# ASIC_3.net
KiCad netlist of a schematic drawn in Altium Designer
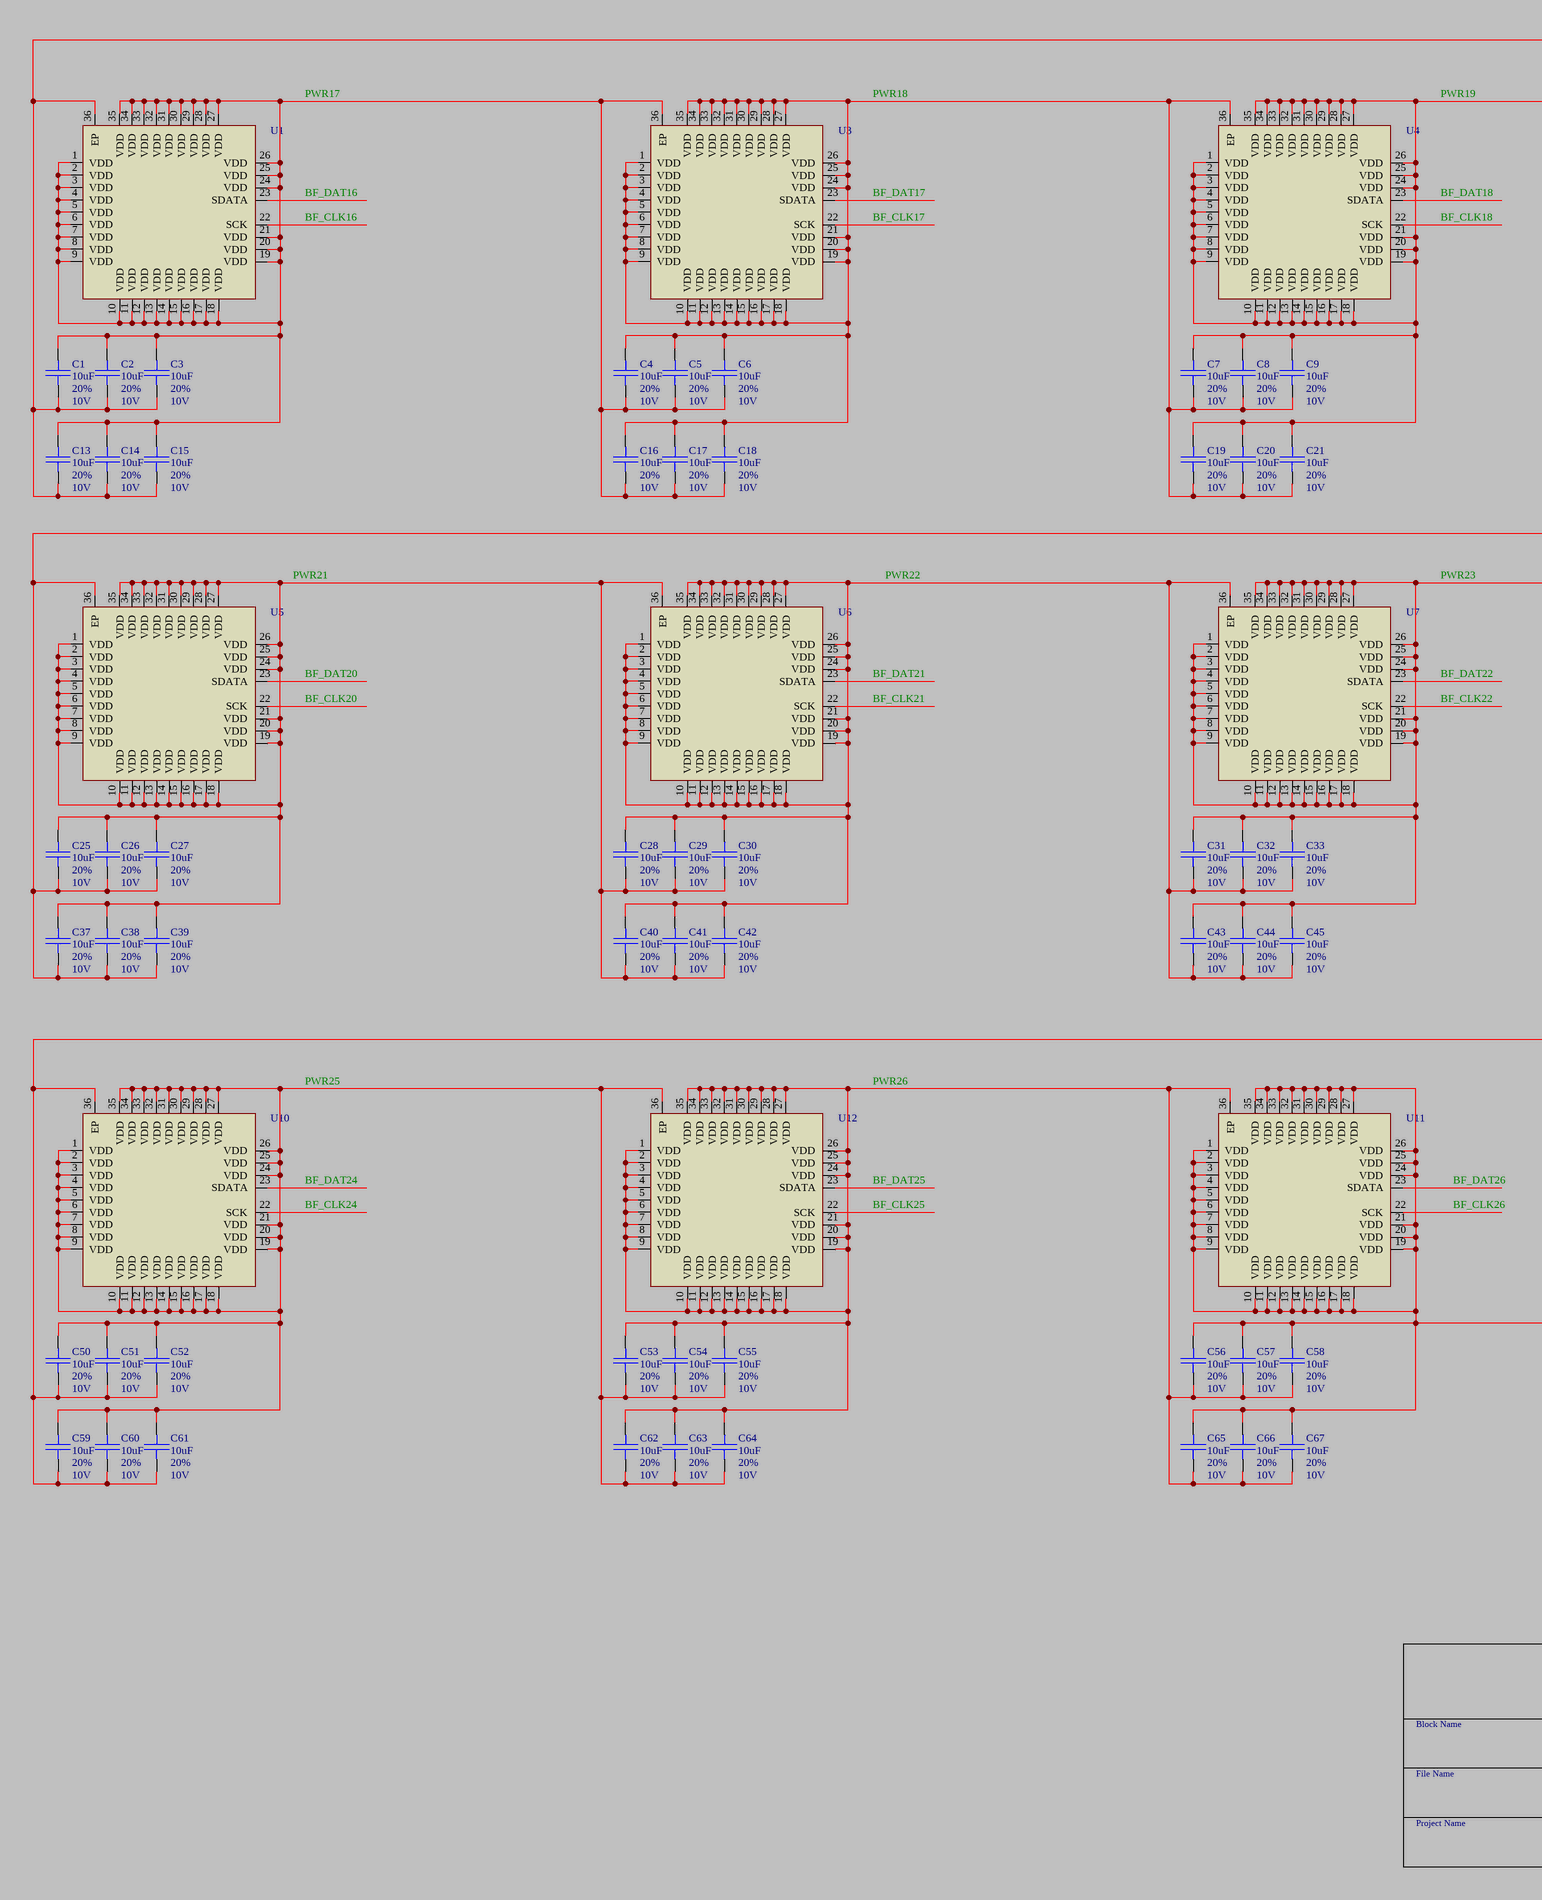
[diagram p0: ASIC_3.SchDoc, left]
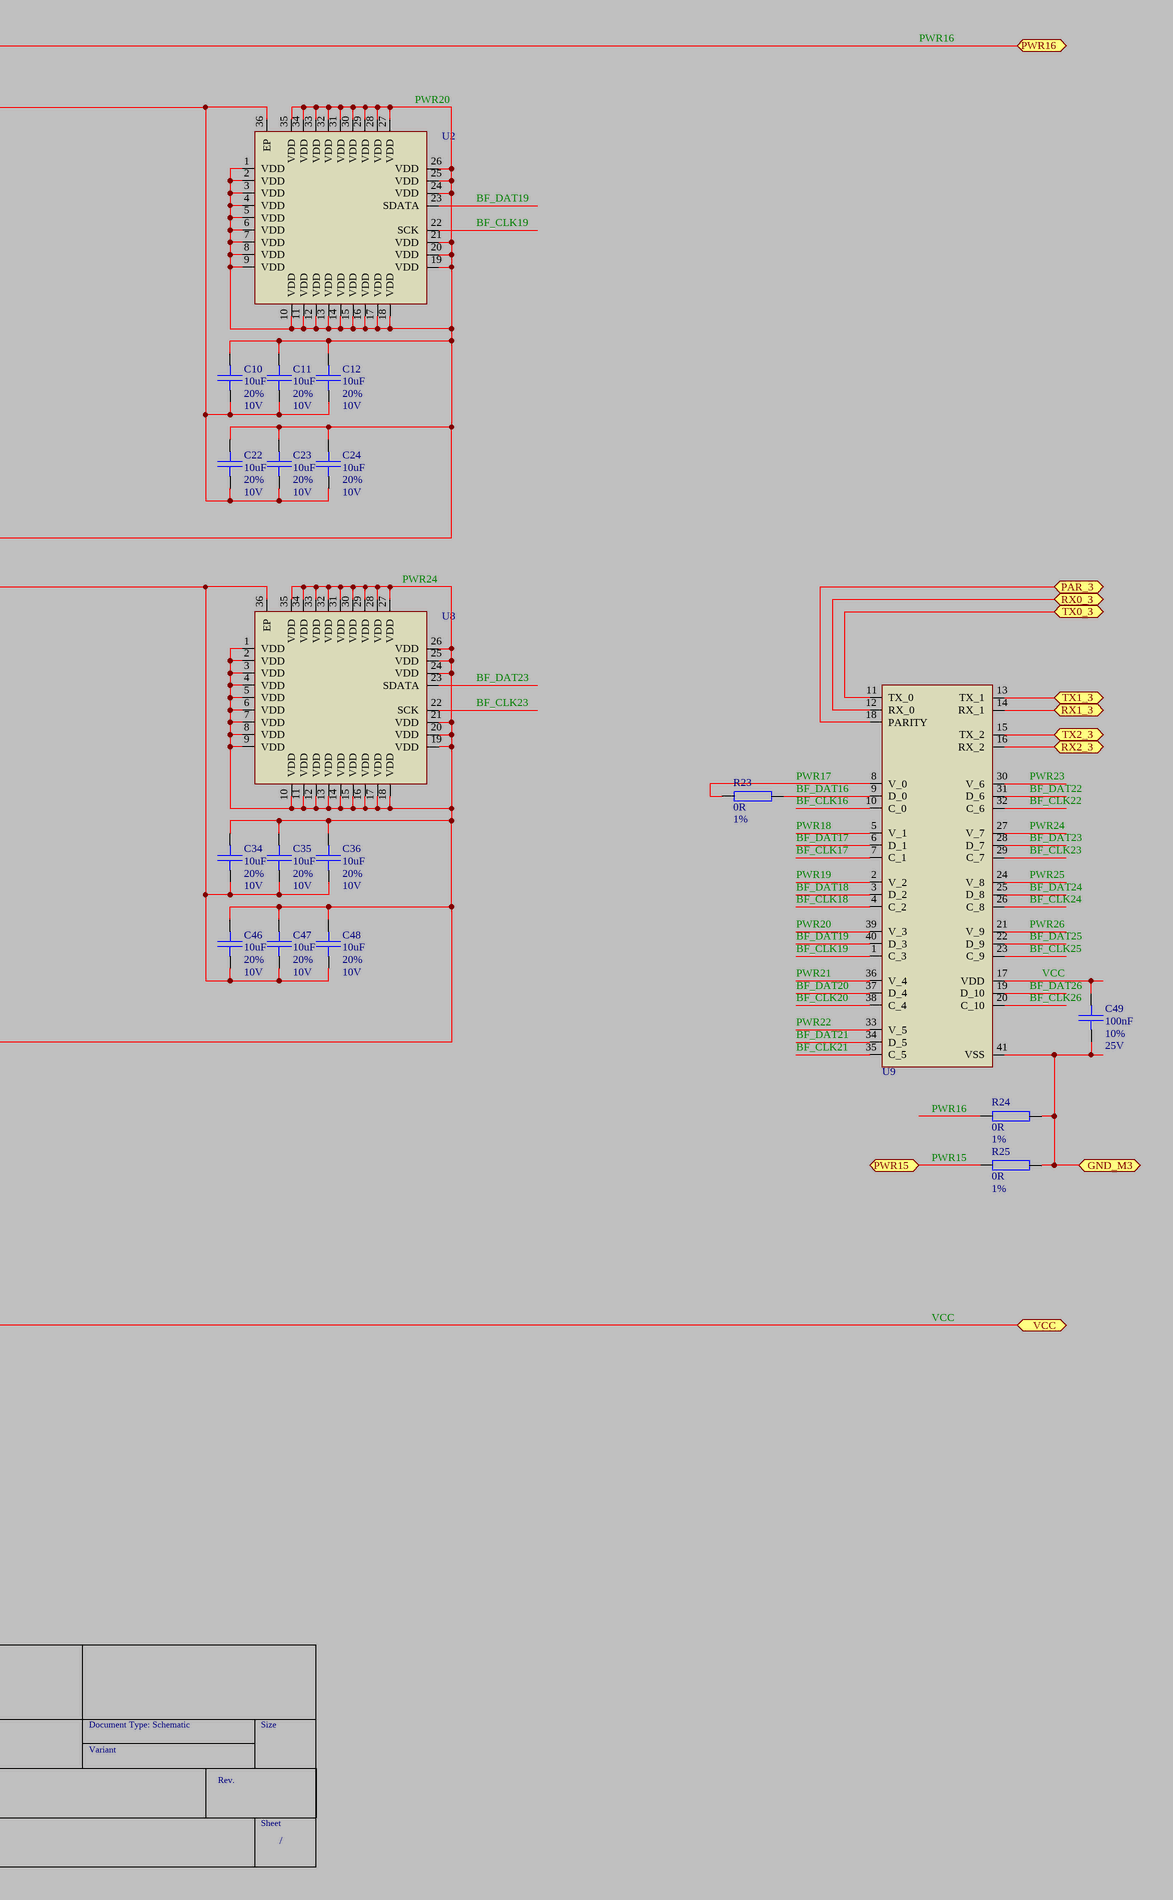
[diagram p1: ASIC_3.SchDoc, right]

(export (version "E")
  (design (tool "Eeschema 10.0.6"))
  (components
    (comp (ref "C1")
      (value "C")
      (footprint "SMD_0402_CAPC1005X70N")
      (fields
        (field (name "DB_PART_NUMBER") "CAP000047481")
        (field (name "DB_VALUE") "10uF")
        (field (name "DB_TOLERANCE") "20%")
        (field (name "DB_VOLTAGE") "10V")
        (field (name "DB_MANUFACTURER_PART") "SAMSUNG    CL05A106MP5NUNC")
        (field (name "DB_APPROVED_BY") "VSN")
      )
      (libsource (lib "Database_Libs1") (part "C"))
    )
    (comp (ref "C2")
      (value "C")
      (footprint "SMD_0402_CAPC1005X70N")
      (fields
        (field (name "DB_PART_NUMBER") "CAP000047481")
        (field (name "DB_VALUE") "10uF")
        (field (name "DB_TOLERANCE") "20%")
        (field (name "DB_VOLTAGE") "10V")
        (field (name "DB_MANUFACTURER_PART") "SAMSUNG    CL05A106MP5NUNC")
        (field (name "DB_APPROVED_BY") "VSN")
      )
      (libsource (lib "Database_Libs1") (part "C"))
    )
    (comp (ref "C3")
      (value "C")
      (footprint "SMD_0402_CAPC1005X70N")
      (fields
        (field (name "DB_PART_NUMBER") "CAP000047481")
        (field (name "DB_VALUE") "10uF")
        (field (name "DB_TOLERANCE") "20%")
        (field (name "DB_VOLTAGE") "10V")
        (field (name "DB_MANUFACTURER_PART") "SAMSUNG    CL05A106MP5NUNC")
        (field (name "DB_APPROVED_BY") "VSN")
      )
      (libsource (lib "Database_Libs1") (part "C"))
    )
    (comp (ref "C4")
      (value "C")
      (footprint "SMD_0402_CAPC1005X70N")
      (fields
        (field (name "DB_PART_NUMBER") "CAP000047481")
        (field (name "DB_VALUE") "10uF")
        (field (name "DB_TOLERANCE") "20%")
        (field (name "DB_VOLTAGE") "10V")
        (field (name "DB_MANUFACTURER_PART") "SAMSUNG    CL05A106MP5NUNC")
        (field (name "DB_APPROVED_BY") "VSN")
      )
      (libsource (lib "Database_Libs1") (part "C"))
    )
    (comp (ref "C5")
      (value "C")
      (footprint "SMD_0402_CAPC1005X70N")
      (fields
        (field (name "DB_PART_NUMBER") "CAP000047481")
        (field (name "DB_VALUE") "10uF")
        (field (name "DB_TOLERANCE") "20%")
        (field (name "DB_VOLTAGE") "10V")
        (field (name "DB_MANUFACTURER_PART") "SAMSUNG    CL05A106MP5NUNC")
        (field (name "DB_APPROVED_BY") "VSN")
      )
      (libsource (lib "Database_Libs1") (part "C"))
    )
    (comp (ref "C6")
      (value "C")
      (footprint "SMD_0402_CAPC1005X70N")
      (fields
        (field (name "DB_PART_NUMBER") "CAP000047481")
        (field (name "DB_VALUE") "10uF")
        (field (name "DB_TOLERANCE") "20%")
        (field (name "DB_VOLTAGE") "10V")
        (field (name "DB_MANUFACTURER_PART") "SAMSUNG    CL05A106MP5NUNC")
        (field (name "DB_APPROVED_BY") "VSN")
      )
      (libsource (lib "Database_Libs1") (part "C"))
    )
    (comp (ref "C7")
      (value "C")
      (footprint "SMD_0402_CAPC1005X70N")
      (fields
        (field (name "DB_PART_NUMBER") "CAP000047481")
        (field (name "DB_VALUE") "10uF")
        (field (name "DB_TOLERANCE") "20%")
        (field (name "DB_VOLTAGE") "10V")
        (field (name "DB_MANUFACTURER_PART") "SAMSUNG    CL05A106MP5NUNC")
        (field (name "DB_APPROVED_BY") "VSN")
      )
      (libsource (lib "Database_Libs1") (part "C"))
    )
    (comp (ref "C8")
      (value "C")
      (footprint "SMD_0402_CAPC1005X70N")
      (fields
        (field (name "DB_PART_NUMBER") "CAP000047481")
        (field (name "DB_VALUE") "10uF")
        (field (name "DB_TOLERANCE") "20%")
        (field (name "DB_VOLTAGE") "10V")
        (field (name "DB_MANUFACTURER_PART") "SAMSUNG    CL05A106MP5NUNC")
        (field (name "DB_APPROVED_BY") "VSN")
      )
      (libsource (lib "Database_Libs1") (part "C"))
    )
    (comp (ref "C9")
      (value "C")
      (footprint "SMD_0402_CAPC1005X70N")
      (fields
        (field (name "DB_PART_NUMBER") "CAP000047481")
        (field (name "DB_VALUE") "10uF")
        (field (name "DB_TOLERANCE") "20%")
        (field (name "DB_VOLTAGE") "10V")
        (field (name "DB_MANUFACTURER_PART") "SAMSUNG    CL05A106MP5NUNC")
        (field (name "DB_APPROVED_BY") "VSN")
      )
      (libsource (lib "Database_Libs1") (part "C"))
    )
    (comp (ref "C10")
      (value "C")
      (footprint "SMD_0402_CAPC1005X70N")
      (fields
        (field (name "DB_PART_NUMBER") "CAP000047481")
        (field (name "DB_VALUE") "10uF")
        (field (name "DB_TOLERANCE") "20%")
        (field (name "DB_VOLTAGE") "10V")
        (field (name "DB_MANUFACTURER_PART") "SAMSUNG    CL05A106MP5NUNC")
        (field (name "DB_APPROVED_BY") "VSN")
      )
      (libsource (lib "Database_Libs1") (part "C"))
    )
    (comp (ref "C11")
      (value "C")
      (footprint "SMD_0402_CAPC1005X70N")
      (fields
        (field (name "DB_PART_NUMBER") "CAP000047481")
        (field (name "DB_VALUE") "10uF")
        (field (name "DB_TOLERANCE") "20%")
        (field (name "DB_VOLTAGE") "10V")
        (field (name "DB_MANUFACTURER_PART") "SAMSUNG    CL05A106MP5NUNC")
        (field (name "DB_APPROVED_BY") "VSN")
      )
      (libsource (lib "Database_Libs1") (part "C"))
    )
    (comp (ref "C12")
      (value "C")
      (footprint "SMD_0402_CAPC1005X70N")
      (fields
        (field (name "DB_PART_NUMBER") "CAP000047481")
        (field (name "DB_VALUE") "10uF")
        (field (name "DB_TOLERANCE") "20%")
        (field (name "DB_VOLTAGE") "10V")
        (field (name "DB_MANUFACTURER_PART") "SAMSUNG    CL05A106MP5NUNC")
        (field (name "DB_APPROVED_BY") "VSN")
      )
      (libsource (lib "Database_Libs1") (part "C"))
    )
    (comp (ref "C13")
      (value "C")
      (footprint "SMD_0402_CAPC1005X70N")
      (fields
        (field (name "DB_PART_NUMBER") "CAP000047481")
        (field (name "DB_VALUE") "10uF")
        (field (name "DB_TOLERANCE") "20%")
        (field (name "DB_VOLTAGE") "10V")
        (field (name "DB_MANUFACTURER_PART") "SAMSUNG    CL05A106MP5NUNC")
        (field (name "DB_APPROVED_BY") "VSN")
      )
      (libsource (lib "Database_Libs1") (part "C"))
    )
    (comp (ref "C14")
      (value "C")
      (footprint "SMD_0402_CAPC1005X70N")
      (fields
        (field (name "DB_PART_NUMBER") "CAP000047481")
        (field (name "DB_VALUE") "10uF")
        (field (name "DB_TOLERANCE") "20%")
        (field (name "DB_VOLTAGE") "10V")
        (field (name "DB_MANUFACTURER_PART") "SAMSUNG    CL05A106MP5NUNC")
        (field (name "DB_APPROVED_BY") "VSN")
      )
      (libsource (lib "Database_Libs1") (part "C"))
    )
    (comp (ref "C15")
      (value "C")
      (footprint "SMD_0402_CAPC1005X70N")
      (fields
        (field (name "DB_PART_NUMBER") "CAP000047481")
        (field (name "DB_VALUE") "10uF")
        (field (name "DB_TOLERANCE") "20%")
        (field (name "DB_VOLTAGE") "10V")
        (field (name "DB_MANUFACTURER_PART") "SAMSUNG    CL05A106MP5NUNC")
        (field (name "DB_APPROVED_BY") "VSN")
      )
      (libsource (lib "Database_Libs1") (part "C"))
    )
    (comp (ref "C16")
      (value "C")
      (footprint "SMD_0402_CAPC1005X70N")
      (fields
        (field (name "DB_PART_NUMBER") "CAP000047481")
        (field (name "DB_VALUE") "10uF")
        (field (name "DB_TOLERANCE") "20%")
        (field (name "DB_VOLTAGE") "10V")
        (field (name "DB_MANUFACTURER_PART") "SAMSUNG    CL05A106MP5NUNC")
        (field (name "DB_APPROVED_BY") "VSN")
      )
      (libsource (lib "Database_Libs1") (part "C"))
    )
    (comp (ref "C17")
      (value "C")
      (footprint "SMD_0402_CAPC1005X70N")
      (fields
        (field (name "DB_PART_NUMBER") "CAP000047481")
        (field (name "DB_VALUE") "10uF")
        (field (name "DB_TOLERANCE") "20%")
        (field (name "DB_VOLTAGE") "10V")
        (field (name "DB_MANUFACTURER_PART") "SAMSUNG    CL05A106MP5NUNC")
        (field (name "DB_APPROVED_BY") "VSN")
      )
      (libsource (lib "Database_Libs1") (part "C"))
    )
    (comp (ref "C18")
      (value "C")
      (footprint "SMD_0402_CAPC1005X70N")
      (fields
        (field (name "DB_PART_NUMBER") "CAP000047481")
        (field (name "DB_VALUE") "10uF")
        (field (name "DB_TOLERANCE") "20%")
        (field (name "DB_VOLTAGE") "10V")
        (field (name "DB_MANUFACTURER_PART") "SAMSUNG    CL05A106MP5NUNC")
        (field (name "DB_APPROVED_BY") "VSN")
      )
      (libsource (lib "Database_Libs1") (part "C"))
    )
    (comp (ref "C19")
      (value "C")
      (footprint "SMD_0402_CAPC1005X70N")
      (fields
        (field (name "DB_PART_NUMBER") "CAP000047481")
        (field (name "DB_VALUE") "10uF")
        (field (name "DB_TOLERANCE") "20%")
        (field (name "DB_VOLTAGE") "10V")
        (field (name "DB_MANUFACTURER_PART") "SAMSUNG    CL05A106MP5NUNC")
        (field (name "DB_APPROVED_BY") "VSN")
      )
      (libsource (lib "Database_Libs1") (part "C"))
    )
    (comp (ref "C20")
      (value "C")
      (footprint "SMD_0402_CAPC1005X70N")
      (fields
        (field (name "DB_PART_NUMBER") "CAP000047481")
        (field (name "DB_VALUE") "10uF")
        (field (name "DB_TOLERANCE") "20%")
        (field (name "DB_VOLTAGE") "10V")
        (field (name "DB_MANUFACTURER_PART") "SAMSUNG    CL05A106MP5NUNC")
        (field (name "DB_APPROVED_BY") "VSN")
      )
      (libsource (lib "Database_Libs1") (part "C"))
    )
    (comp (ref "C21")
      (value "C")
      (footprint "SMD_0402_CAPC1005X70N")
      (fields
        (field (name "DB_PART_NUMBER") "CAP000047481")
        (field (name "DB_VALUE") "10uF")
        (field (name "DB_TOLERANCE") "20%")
        (field (name "DB_VOLTAGE") "10V")
        (field (name "DB_MANUFACTURER_PART") "SAMSUNG    CL05A106MP5NUNC")
        (field (name "DB_APPROVED_BY") "VSN")
      )
      (libsource (lib "Database_Libs1") (part "C"))
    )
    (comp (ref "C22")
      (value "C")
      (footprint "SMD_0402_CAPC1005X70N")
      (fields
        (field (name "DB_PART_NUMBER") "CAP000047481")
        (field (name "DB_VALUE") "10uF")
        (field (name "DB_TOLERANCE") "20%")
        (field (name "DB_VOLTAGE") "10V")
        (field (name "DB_MANUFACTURER_PART") "SAMSUNG    CL05A106MP5NUNC")
        (field (name "DB_APPROVED_BY") "VSN")
      )
      (libsource (lib "Database_Libs1") (part "C"))
    )
    (comp (ref "C23")
      (value "C")
      (footprint "SMD_0402_CAPC1005X70N")
      (fields
        (field (name "DB_PART_NUMBER") "CAP000047481")
        (field (name "DB_VALUE") "10uF")
        (field (name "DB_TOLERANCE") "20%")
        (field (name "DB_VOLTAGE") "10V")
        (field (name "DB_MANUFACTURER_PART") "SAMSUNG    CL05A106MP5NUNC")
        (field (name "DB_APPROVED_BY") "VSN")
      )
      (libsource (lib "Database_Libs1") (part "C"))
    )
    (comp (ref "C24")
      (value "C")
      (footprint "SMD_0402_CAPC1005X70N")
      (fields
        (field (name "DB_PART_NUMBER") "CAP000047481")
        (field (name "DB_VALUE") "10uF")
        (field (name "DB_TOLERANCE") "20%")
        (field (name "DB_VOLTAGE") "10V")
        (field (name "DB_MANUFACTURER_PART") "SAMSUNG    CL05A106MP5NUNC")
        (field (name "DB_APPROVED_BY") "VSN")
      )
      (libsource (lib "Database_Libs1") (part "C"))
    )
    (comp (ref "C25")
      (value "C")
      (footprint "SMD_0402_CAPC1005X70N")
      (fields
        (field (name "DB_PART_NUMBER") "CAP000047481")
        (field (name "DB_VALUE") "10uF")
        (field (name "DB_TOLERANCE") "20%")
        (field (name "DB_VOLTAGE") "10V")
        (field (name "DB_MANUFACTURER_PART") "SAMSUNG    CL05A106MP5NUNC")
        (field (name "DB_APPROVED_BY") "VSN")
      )
      (libsource (lib "Database_Libs1") (part "C"))
    )
    (comp (ref "C26")
      (value "C")
      (footprint "SMD_0402_CAPC1005X70N")
      (fields
        (field (name "DB_PART_NUMBER") "CAP000047481")
        (field (name "DB_VALUE") "10uF")
        (field (name "DB_TOLERANCE") "20%")
        (field (name "DB_VOLTAGE") "10V")
        (field (name "DB_MANUFACTURER_PART") "SAMSUNG    CL05A106MP5NUNC")
        (field (name "DB_APPROVED_BY") "VSN")
      )
      (libsource (lib "Database_Libs1") (part "C"))
    )
    (comp (ref "C27")
      (value "C")
      (footprint "SMD_0402_CAPC1005X70N")
      (fields
        (field (name "DB_PART_NUMBER") "CAP000047481")
        (field (name "DB_VALUE") "10uF")
        (field (name "DB_TOLERANCE") "20%")
        (field (name "DB_VOLTAGE") "10V")
        (field (name "DB_MANUFACTURER_PART") "SAMSUNG    CL05A106MP5NUNC")
        (field (name "DB_APPROVED_BY") "VSN")
      )
      (libsource (lib "Database_Libs1") (part "C"))
    )
    (comp (ref "C28")
      (value "C")
      (footprint "SMD_0402_CAPC1005X70N")
      (fields
        (field (name "DB_PART_NUMBER") "CAP000047481")
        (field (name "DB_VALUE") "10uF")
        (field (name "DB_TOLERANCE") "20%")
        (field (name "DB_VOLTAGE") "10V")
        (field (name "DB_MANUFACTURER_PART") "SAMSUNG    CL05A106MP5NUNC")
        (field (name "DB_APPROVED_BY") "VSN")
      )
      (libsource (lib "Database_Libs1") (part "C"))
    )
    (comp (ref "C29")
      (value "C")
      (footprint "SMD_0402_CAPC1005X70N")
      (fields
        (field (name "DB_PART_NUMBER") "CAP000047481")
        (field (name "DB_VALUE") "10uF")
        (field (name "DB_TOLERANCE") "20%")
        (field (name "DB_VOLTAGE") "10V")
        (field (name "DB_MANUFACTURER_PART") "SAMSUNG    CL05A106MP5NUNC")
        (field (name "DB_APPROVED_BY") "VSN")
      )
      (libsource (lib "Database_Libs1") (part "C"))
    )
    (comp (ref "C30")
      (value "C")
      (footprint "SMD_0402_CAPC1005X70N")
      (fields
        (field (name "DB_PART_NUMBER") "CAP000047481")
        (field (name "DB_VALUE") "10uF")
        (field (name "DB_TOLERANCE") "20%")
        (field (name "DB_VOLTAGE") "10V")
        (field (name "DB_MANUFACTURER_PART") "SAMSUNG    CL05A106MP5NUNC")
        (field (name "DB_APPROVED_BY") "VSN")
      )
      (libsource (lib "Database_Libs1") (part "C"))
    )
    (comp (ref "C31")
      (value "C")
      (footprint "SMD_0402_CAPC1005X70N")
      (fields
        (field (name "DB_PART_NUMBER") "CAP000047481")
        (field (name "DB_VALUE") "10uF")
        (field (name "DB_TOLERANCE") "20%")
        (field (name "DB_VOLTAGE") "10V")
        (field (name "DB_MANUFACTURER_PART") "SAMSUNG    CL05A106MP5NUNC")
        (field (name "DB_APPROVED_BY") "VSN")
      )
      (libsource (lib "Database_Libs1") (part "C"))
    )
    (comp (ref "C32")
      (value "C")
      (footprint "SMD_0402_CAPC1005X70N")
      (fields
        (field (name "DB_PART_NUMBER") "CAP000047481")
        (field (name "DB_VALUE") "10uF")
        (field (name "DB_TOLERANCE") "20%")
        (field (name "DB_VOLTAGE") "10V")
        (field (name "DB_MANUFACTURER_PART") "SAMSUNG    CL05A106MP5NUNC")
        (field (name "DB_APPROVED_BY") "VSN")
      )
      (libsource (lib "Database_Libs1") (part "C"))
    )
    (comp (ref "C33")
      (value "C")
      (footprint "SMD_0402_CAPC1005X70N")
      (fields
        (field (name "DB_PART_NUMBER") "CAP000047481")
        (field (name "DB_VALUE") "10uF")
        (field (name "DB_TOLERANCE") "20%")
        (field (name "DB_VOLTAGE") "10V")
        (field (name "DB_MANUFACTURER_PART") "SAMSUNG    CL05A106MP5NUNC")
        (field (name "DB_APPROVED_BY") "VSN")
      )
      (libsource (lib "Database_Libs1") (part "C"))
    )
    (comp (ref "C34")
      (value "C")
      (footprint "SMD_0402_CAPC1005X70N")
      (fields
        (field (name "DB_PART_NUMBER") "CAP000047481")
        (field (name "DB_VALUE") "10uF")
        (field (name "DB_TOLERANCE") "20%")
        (field (name "DB_VOLTAGE") "10V")
        (field (name "DB_MANUFACTURER_PART") "SAMSUNG    CL05A106MP5NUNC")
        (field (name "DB_APPROVED_BY") "VSN")
      )
      (libsource (lib "Database_Libs1") (part "C"))
    )
    (comp (ref "C35")
      (value "C")
      (footprint "SMD_0402_CAPC1005X70N")
      (fields
        (field (name "DB_PART_NUMBER") "CAP000047481")
        (field (name "DB_VALUE") "10uF")
        (field (name "DB_TOLERANCE") "20%")
        (field (name "DB_VOLTAGE") "10V")
        (field (name "DB_MANUFACTURER_PART") "SAMSUNG    CL05A106MP5NUNC")
        (field (name "DB_APPROVED_BY") "VSN")
      )
      (libsource (lib "Database_Libs1") (part "C"))
    )
    (comp (ref "C36")
      (value "C")
      (footprint "SMD_0402_CAPC1005X70N")
      (fields
        (field (name "DB_PART_NUMBER") "CAP000047481")
        (field (name "DB_VALUE") "10uF")
        (field (name "DB_TOLERANCE") "20%")
        (field (name "DB_VOLTAGE") "10V")
        (field (name "DB_MANUFACTURER_PART") "SAMSUNG    CL05A106MP5NUNC")
        (field (name "DB_APPROVED_BY") "VSN")
      )
      (libsource (lib "Database_Libs1") (part "C"))
    )
    (comp (ref "C37")
      (value "C")
      (footprint "SMD_0402_CAPC1005X70N")
      (fields
        (field (name "DB_PART_NUMBER") "CAP000047481")
        (field (name "DB_VALUE") "10uF")
        (field (name "DB_TOLERANCE") "20%")
        (field (name "DB_VOLTAGE") "10V")
        (field (name "DB_MANUFACTURER_PART") "SAMSUNG    CL05A106MP5NUNC")
        (field (name "DB_APPROVED_BY") "VSN")
      )
      (libsource (lib "Database_Libs1") (part "C"))
    )
    (comp (ref "C38")
      (value "C")
      (footprint "SMD_0402_CAPC1005X70N")
      (fields
        (field (name "DB_PART_NUMBER") "CAP000047481")
        (field (name "DB_VALUE") "10uF")
        (field (name "DB_TOLERANCE") "20%")
        (field (name "DB_VOLTAGE") "10V")
        (field (name "DB_MANUFACTURER_PART") "SAMSUNG    CL05A106MP5NUNC")
        (field (name "DB_APPROVED_BY") "VSN")
      )
      (libsource (lib "Database_Libs1") (part "C"))
    )
    (comp (ref "C39")
      (value "C")
      (footprint "SMD_0402_CAPC1005X70N")
      (fields
        (field (name "DB_PART_NUMBER") "CAP000047481")
        (field (name "DB_VALUE") "10uF")
        (field (name "DB_TOLERANCE") "20%")
        (field (name "DB_VOLTAGE") "10V")
        (field (name "DB_MANUFACTURER_PART") "SAMSUNG    CL05A106MP5NUNC")
        (field (name "DB_APPROVED_BY") "VSN")
      )
      (libsource (lib "Database_Libs1") (part "C"))
    )
    (comp (ref "C40")
      (value "C")
      (footprint "SMD_0402_CAPC1005X70N")
      (fields
        (field (name "DB_PART_NUMBER") "CAP000047481")
        (field (name "DB_VALUE") "10uF")
        (field (name "DB_TOLERANCE") "20%")
        (field (name "DB_VOLTAGE") "10V")
        (field (name "DB_MANUFACTURER_PART") "SAMSUNG    CL05A106MP5NUNC")
        (field (name "DB_APPROVED_BY") "VSN")
      )
      (libsource (lib "Database_Libs1") (part "C"))
    )
    (comp (ref "C41")
      (value "C")
      (footprint "SMD_0402_CAPC1005X70N")
      (fields
        (field (name "DB_PART_NUMBER") "CAP000047481")
        (field (name "DB_VALUE") "10uF")
        (field (name "DB_TOLERANCE") "20%")
        (field (name "DB_VOLTAGE") "10V")
        (field (name "DB_MANUFACTURER_PART") "SAMSUNG    CL05A106MP5NUNC")
        (field (name "DB_APPROVED_BY") "VSN")
      )
      (libsource (lib "Database_Libs1") (part "C"))
    )
    (comp (ref "C42")
      (value "C")
      (footprint "SMD_0402_CAPC1005X70N")
      (fields
        (field (name "DB_PART_NUMBER") "CAP000047481")
        (field (name "DB_VALUE") "10uF")
        (field (name "DB_TOLERANCE") "20%")
        (field (name "DB_VOLTAGE") "10V")
        (field (name "DB_MANUFACTURER_PART") "SAMSUNG    CL05A106MP5NUNC")
        (field (name "DB_APPROVED_BY") "VSN")
      )
      (libsource (lib "Database_Libs1") (part "C"))
    )
    (comp (ref "C43")
      (value "C")
      (footprint "SMD_0402_CAPC1005X70N")
      (fields
        (field (name "DB_PART_NUMBER") "CAP000047481")
        (field (name "DB_VALUE") "10uF")
        (field (name "DB_TOLERANCE") "20%")
        (field (name "DB_VOLTAGE") "10V")
        (field (name "DB_MANUFACTURER_PART") "SAMSUNG    CL05A106MP5NUNC")
        (field (name "DB_APPROVED_BY") "VSN")
      )
      (libsource (lib "Database_Libs1") (part "C"))
    )
    (comp (ref "C44")
      (value "C")
      (footprint "SMD_0402_CAPC1005X70N")
      (fields
        (field (name "DB_PART_NUMBER") "CAP000047481")
        (field (name "DB_VALUE") "10uF")
        (field (name "DB_TOLERANCE") "20%")
        (field (name "DB_VOLTAGE") "10V")
        (field (name "DB_MANUFACTURER_PART") "SAMSUNG    CL05A106MP5NUNC")
        (field (name "DB_APPROVED_BY") "VSN")
      )
      (libsource (lib "Database_Libs1") (part "C"))
    )
    (comp (ref "C45")
      (value "C")
      (footprint "SMD_0402_CAPC1005X70N")
      (fields
        (field (name "DB_PART_NUMBER") "CAP000047481")
        (field (name "DB_VALUE") "10uF")
        (field (name "DB_TOLERANCE") "20%")
        (field (name "DB_VOLTAGE") "10V")
        (field (name "DB_MANUFACTURER_PART") "SAMSUNG    CL05A106MP5NUNC")
        (field (name "DB_APPROVED_BY") "VSN")
      )
      (libsource (lib "Database_Libs1") (part "C"))
    )
    (comp (ref "C46")
      (value "C")
      (footprint "SMD_0402_CAPC1005X70N")
      (fields
        (field (name "DB_PART_NUMBER") "CAP000047481")
        (field (name "DB_VALUE") "10uF")
        (field (name "DB_TOLERANCE") "20%")
        (field (name "DB_VOLTAGE") "10V")
        (field (name "DB_MANUFACTURER_PART") "SAMSUNG    CL05A106MP5NUNC")
        (field (name "DB_APPROVED_BY") "VSN")
      )
      (libsource (lib "Database_Libs1") (part "C"))
    )
    (comp (ref "C47")
      (value "C")
      (footprint "SMD_0402_CAPC1005X70N")
      (fields
        (field (name "DB_PART_NUMBER") "CAP000047481")
        (field (name "DB_VALUE") "10uF")
        (field (name "DB_TOLERANCE") "20%")
        (field (name "DB_VOLTAGE") "10V")
        (field (name "DB_MANUFACTURER_PART") "SAMSUNG    CL05A106MP5NUNC")
        (field (name "DB_APPROVED_BY") "VSN")
      )
      (libsource (lib "Database_Libs1") (part "C"))
    )
    (comp (ref "C48")
      (value "C")
      (footprint "SMD_0402_CAPC1005X70N")
      (fields
        (field (name "DB_PART_NUMBER") "CAP000047481")
        (field (name "DB_VALUE") "10uF")
        (field (name "DB_TOLERANCE") "20%")
        (field (name "DB_VOLTAGE") "10V")
        (field (name "DB_MANUFACTURER_PART") "SAMSUNG    CL05A106MP5NUNC")
        (field (name "DB_APPROVED_BY") "VSN")
      )
      (libsource (lib "Database_Libs1") (part "C"))
    )
    (comp (ref "C49")
      (value "C")
      (footprint "SMD_0402_CAPC1005X55N")
      (fields
        (field (name "DB_PART_NUMBER") "CAP000047469")
        (field (name "DB_VALUE") "100nF")
        (field (name "DB_TOLERANCE") "10%")
        (field (name "DB_VOLTAGE") "25V")
        (field (name "DB_MANUFACTURER_PART") "SAMSUNG    CL05A104KA5NNNC")
        (field (name "DB_APPROVED_BY") "VSN")
      )
      (libsource (lib "Database_Libs1") (part "C"))
    )
    (comp (ref "C50")
      (value "C")
      (footprint "SMD_0402_CAPC1005X70N")
      (fields
        (field (name "DB_PART_NUMBER") "CAP000047481")
        (field (name "DB_VALUE") "10uF")
        (field (name "DB_TOLERANCE") "20%")
        (field (name "DB_VOLTAGE") "10V")
        (field (name "DB_MANUFACTURER_PART") "SAMSUNG    CL05A106MP5NUNC")
        (field (name "DB_APPROVED_BY") "VSN")
      )
      (libsource (lib "Database_Libs1") (part "C"))
    )
    (comp (ref "C51")
      (value "C")
      (footprint "SMD_0402_CAPC1005X70N")
      (fields
        (field (name "DB_PART_NUMBER") "CAP000047481")
        (field (name "DB_VALUE") "10uF")
        (field (name "DB_TOLERANCE") "20%")
        (field (name "DB_VOLTAGE") "10V")
        (field (name "DB_MANUFACTURER_PART") "SAMSUNG    CL05A106MP5NUNC")
        (field (name "DB_APPROVED_BY") "VSN")
      )
      (libsource (lib "Database_Libs1") (part "C"))
    )
    (comp (ref "C52")
      (value "C")
      (footprint "SMD_0402_CAPC1005X70N")
      (fields
        (field (name "DB_PART_NUMBER") "CAP000047481")
        (field (name "DB_VALUE") "10uF")
        (field (name "DB_TOLERANCE") "20%")
        (field (name "DB_VOLTAGE") "10V")
        (field (name "DB_MANUFACTURER_PART") "SAMSUNG    CL05A106MP5NUNC")
        (field (name "DB_APPROVED_BY") "VSN")
      )
      (libsource (lib "Database_Libs1") (part "C"))
    )
    (comp (ref "C53")
      (value "C")
      (footprint "SMD_0402_CAPC1005X70N")
      (fields
        (field (name "DB_PART_NUMBER") "CAP000047481")
        (field (name "DB_VALUE") "10uF")
        (field (name "DB_TOLERANCE") "20%")
        (field (name "DB_VOLTAGE") "10V")
        (field (name "DB_MANUFACTURER_PART") "SAMSUNG    CL05A106MP5NUNC")
        (field (name "DB_APPROVED_BY") "VSN")
      )
      (libsource (lib "Database_Libs1") (part "C"))
    )
    (comp (ref "C54")
      (value "C")
      (footprint "SMD_0402_CAPC1005X70N")
      (fields
        (field (name "DB_PART_NUMBER") "CAP000047481")
        (field (name "DB_VALUE") "10uF")
        (field (name "DB_TOLERANCE") "20%")
        (field (name "DB_VOLTAGE") "10V")
        (field (name "DB_MANUFACTURER_PART") "SAMSUNG    CL05A106MP5NUNC")
        (field (name "DB_APPROVED_BY") "VSN")
      )
      (libsource (lib "Database_Libs1") (part "C"))
    )
    (comp (ref "C55")
      (value "C")
      (footprint "SMD_0402_CAPC1005X70N")
      (fields
        (field (name "DB_PART_NUMBER") "CAP000047481")
        (field (name "DB_VALUE") "10uF")
        (field (name "DB_TOLERANCE") "20%")
        (field (name "DB_VOLTAGE") "10V")
        (field (name "DB_MANUFACTURER_PART") "SAMSUNG    CL05A106MP5NUNC")
        (field (name "DB_APPROVED_BY") "VSN")
      )
      (libsource (lib "Database_Libs1") (part "C"))
    )
    (comp (ref "C56")
      (value "C")
      (footprint "SMD_0402_CAPC1005X70N")
      (fields
        (field (name "DB_PART_NUMBER") "CAP000047481")
        (field (name "DB_VALUE") "10uF")
        (field (name "DB_TOLERANCE") "20%")
        (field (name "DB_VOLTAGE") "10V")
        (field (name "DB_MANUFACTURER_PART") "SAMSUNG    CL05A106MP5NUNC")
        (field (name "DB_APPROVED_BY") "VSN")
      )
      (libsource (lib "Database_Libs1") (part "C"))
    )
    (comp (ref "C57")
      (value "C")
      (footprint "SMD_0402_CAPC1005X70N")
      (fields
        (field (name "DB_PART_NUMBER") "CAP000047481")
        (field (name "DB_VALUE") "10uF")
        (field (name "DB_TOLERANCE") "20%")
        (field (name "DB_VOLTAGE") "10V")
        (field (name "DB_MANUFACTURER_PART") "SAMSUNG    CL05A106MP5NUNC")
        (field (name "DB_APPROVED_BY") "VSN")
      )
      (libsource (lib "Database_Libs1") (part "C"))
    )
    (comp (ref "C58")
      (value "C")
      (footprint "SMD_0402_CAPC1005X70N")
      (fields
        (field (name "DB_PART_NUMBER") "CAP000047481")
        (field (name "DB_VALUE") "10uF")
        (field (name "DB_TOLERANCE") "20%")
        (field (name "DB_VOLTAGE") "10V")
        (field (name "DB_MANUFACTURER_PART") "SAMSUNG    CL05A106MP5NUNC")
        (field (name "DB_APPROVED_BY") "VSN")
      )
      (libsource (lib "Database_Libs1") (part "C"))
    )
    (comp (ref "C59")
      (value "C")
      (footprint "SMD_0402_CAPC1005X70N")
      (fields
        (field (name "DB_PART_NUMBER") "CAP000047481")
        (field (name "DB_VALUE") "10uF")
        (field (name "DB_TOLERANCE") "20%")
        (field (name "DB_VOLTAGE") "10V")
        (field (name "DB_MANUFACTURER_PART") "SAMSUNG    CL05A106MP5NUNC")
        (field (name "DB_APPROVED_BY") "VSN")
      )
      (libsource (lib "Database_Libs1") (part "C"))
    )
    (comp (ref "C60")
      (value "C")
      (footprint "SMD_0402_CAPC1005X70N")
      (fields
        (field (name "DB_PART_NUMBER") "CAP000047481")
        (field (name "DB_VALUE") "10uF")
        (field (name "DB_TOLERANCE") "20%")
        (field (name "DB_VOLTAGE") "10V")
        (field (name "DB_MANUFACTURER_PART") "SAMSUNG    CL05A106MP5NUNC")
        (field (name "DB_APPROVED_BY") "VSN")
      )
      (libsource (lib "Database_Libs1") (part "C"))
    )
    (comp (ref "C61")
      (value "C")
      (footprint "SMD_0402_CAPC1005X70N")
      (fields
        (field (name "DB_PART_NUMBER") "CAP000047481")
        (field (name "DB_VALUE") "10uF")
        (field (name "DB_TOLERANCE") "20%")
        (field (name "DB_VOLTAGE") "10V")
        (field (name "DB_MANUFACTURER_PART") "SAMSUNG    CL05A106MP5NUNC")
        (field (name "DB_APPROVED_BY") "VSN")
      )
      (libsource (lib "Database_Libs1") (part "C"))
    )
    (comp (ref "C62")
      (value "C")
      (footprint "SMD_0402_CAPC1005X70N")
      (fields
        (field (name "DB_PART_NUMBER") "CAP000047481")
        (field (name "DB_VALUE") "10uF")
        (field (name "DB_TOLERANCE") "20%")
        (field (name "DB_VOLTAGE") "10V")
        (field (name "DB_MANUFACTURER_PART") "SAMSUNG    CL05A106MP5NUNC")
        (field (name "DB_APPROVED_BY") "VSN")
      )
      (libsource (lib "Database_Libs1") (part "C"))
    )
    (comp (ref "C63")
      (value "C")
      (footprint "SMD_0402_CAPC1005X70N")
      (fields
        (field (name "DB_PART_NUMBER") "CAP000047481")
        (field (name "DB_VALUE") "10uF")
        (field (name "DB_TOLERANCE") "20%")
        (field (name "DB_VOLTAGE") "10V")
        (field (name "DB_MANUFACTURER_PART") "SAMSUNG    CL05A106MP5NUNC")
        (field (name "DB_APPROVED_BY") "VSN")
      )
      (libsource (lib "Database_Libs1") (part "C"))
    )
    (comp (ref "C64")
      (value "C")
      (footprint "SMD_0402_CAPC1005X70N")
      (fields
        (field (name "DB_PART_NUMBER") "CAP000047481")
        (field (name "DB_VALUE") "10uF")
        (field (name "DB_TOLERANCE") "20%")
        (field (name "DB_VOLTAGE") "10V")
        (field (name "DB_MANUFACTURER_PART") "SAMSUNG    CL05A106MP5NUNC")
        (field (name "DB_APPROVED_BY") "VSN")
      )
      (libsource (lib "Database_Libs1") (part "C"))
    )
    (comp (ref "C65")
      (value "C")
      (footprint "SMD_0402_CAPC1005X70N")
      (fields
        (field (name "DB_PART_NUMBER") "CAP000047481")
        (field (name "DB_VALUE") "10uF")
        (field (name "DB_TOLERANCE") "20%")
        (field (name "DB_VOLTAGE") "10V")
        (field (name "DB_MANUFACTURER_PART") "SAMSUNG    CL05A106MP5NUNC")
        (field (name "DB_APPROVED_BY") "VSN")
      )
      (libsource (lib "Database_Libs1") (part "C"))
    )
    (comp (ref "C66")
      (value "C")
      (footprint "SMD_0402_CAPC1005X70N")
      (fields
        (field (name "DB_PART_NUMBER") "CAP000047481")
        (field (name "DB_VALUE") "10uF")
        (field (name "DB_TOLERANCE") "20%")
        (field (name "DB_VOLTAGE") "10V")
        (field (name "DB_MANUFACTURER_PART") "SAMSUNG    CL05A106MP5NUNC")
        (field (name "DB_APPROVED_BY") "VSN")
      )
      (libsource (lib "Database_Libs1") (part "C"))
    )
    (comp (ref "C67")
      (value "C")
      (footprint "SMD_0402_CAPC1005X70N")
      (fields
        (field (name "DB_PART_NUMBER") "CAP000047481")
        (field (name "DB_VALUE") "10uF")
        (field (name "DB_TOLERANCE") "20%")
        (field (name "DB_VOLTAGE") "10V")
        (field (name "DB_MANUFACTURER_PART") "SAMSUNG    CL05A106MP5NUNC")
        (field (name "DB_APPROVED_BY") "VSN")
      )
      (libsource (lib "Database_Libs1") (part "C"))
    )
    (comp (ref "R23")
      (value "R")
      (footprint "SMD_0603_RESC1608X55N")
      (fields
        (field (name "DB_PART_NUMBER") "RES000008926")
        (field (name "DB_VALUE") "0R")
        (field (name "DB_TOLERANCE") "1%")
        (field (name "DB_MANUFACTURER_PART") "YAGEO    AC0603FR-070RL")
        (field (name "DB_APPROVED_BY") "VSN")
      )
      (libsource (lib "Database_Libs1") (part "R"))
    )
    (comp (ref "R24")
      (value "R")
      (footprint "SMD_0603_RESC1608X55N")
      (fields
        (field (name "DB_PART_NUMBER") "RES000008926")
        (field (name "DB_VALUE") "0R")
        (field (name "DB_TOLERANCE") "1%")
        (field (name "DB_MANUFACTURER_PART") "YAGEO    AC0603FR-070RL")
        (field (name "DB_APPROVED_BY") "VSN")
      )
      (libsource (lib "Database_Libs1") (part "R"))
    )
    (comp (ref "R25")
      (value "R")
      (footprint "SMD_0603_RESC1608X55N")
      (fields
        (field (name "DB_PART_NUMBER") "RES000008926")
        (field (name "DB_VALUE") "0R")
        (field (name "DB_TOLERANCE") "1%")
        (field (name "DB_MANUFACTURER_PART") "YAGEO    AC0603FR-070RL")
        (field (name "DB_APPROVED_BY") "VSN")
      )
      (libsource (lib "Database_Libs1") (part "R"))
    )
    (comp (ref "U1")
      (value "IC_BITFURY16")
      (footprint "SMD_QFN50P600X600X175-36AN")
      (description "BitFury 2016 16 nm")
      (libsource (lib "BitCoin") (part "IC_BITFURY16"))
    )
    (comp (ref "U2")
      (value "IC_BITFURY16")
      (footprint "SMD_QFN50P600X600X175-36AN")
      (description "BitFury 2016 16 nm")
      (libsource (lib "BitCoin") (part "IC_BITFURY16"))
    )
    (comp (ref "U3")
      (value "IC_BITFURY16")
      (footprint "SMD_QFN50P600X600X175-36AN")
      (description "BitFury 2016 16 nm")
      (libsource (lib "BitCoin") (part "IC_BITFURY16"))
    )
    (comp (ref "U4")
      (value "IC_BITFURY16")
      (footprint "SMD_QFN50P600X600X175-36AN")
      (description "BitFury 2016 16 nm")
      (libsource (lib "BitCoin") (part "IC_BITFURY16"))
    )
    (comp (ref "U5")
      (value "IC_BITFURY16")
      (footprint "SMD_QFN50P600X600X175-36AN")
      (description "BitFury 2016 16 nm")
      (libsource (lib "BitCoin") (part "IC_BITFURY16"))
    )
    (comp (ref "U6")
      (value "IC_BITFURY16")
      (footprint "SMD_QFN50P600X600X175-36AN")
      (description "BitFury 2016 16 nm")
      (libsource (lib "BitCoin") (part "IC_BITFURY16"))
    )
    (comp (ref "U7")
      (value "IC_BITFURY16")
      (footprint "SMD_QFN50P600X600X175-36AN")
      (description "BitFury 2016 16 nm")
      (libsource (lib "BitCoin") (part "IC_BITFURY16"))
    )
    (comp (ref "U8")
      (value "IC_BITFURY16")
      (footprint "SMD_QFN50P600X600X175-36AN")
      (description "BitFury 2016 16 nm")
      (libsource (lib "BitCoin") (part "IC_BITFURY16"))
    )
    (comp (ref "U9")
      (value "IC_BTC250")
      (footprint "SMD_QFN40P500X500X80-41N")
      (libsource (lib "BitCoin") (part "IC_BTC250"))
    )
    (comp (ref "U10")
      (value "IC_BITFURY16")
      (footprint "SMD_QFN50P600X600X175-36AN")
      (description "BitFury 2016 16 nm")
      (libsource (lib "BitCoin") (part "IC_BITFURY16"))
    )
    (comp (ref "U11")
      (value "IC_BITFURY16")
      (footprint "SMD_QFN50P600X600X175-36AN")
      (description "BitFury 2016 16 nm")
      (libsource (lib "BitCoin") (part "IC_BITFURY16"))
    )
    (comp (ref "U12")
      (value "IC_BITFURY16")
      (footprint "SMD_QFN50P600X600X175-36AN")
      (description "BitFury 2016 16 nm")
      (libsource (lib "BitCoin") (part "IC_BITFURY16"))
    )
  )
  (nets
    (net (code "1") (name "/BF_CLK16") (class "Default")
      (node (ref "U1") (pin "22") (pinfunction "SCK_22") (pintype "passive"))
      (node (ref "U9") (pin "10") (pinfunction "C_0_10") (pintype "passive"))
    )
    (net (code "2") (name "/BF_CLK17") (class "Default")
      (node (ref "U3") (pin "22") (pinfunction "SCK_22") (pintype "passive"))
      (node (ref "U9") (pin "7") (pinfunction "C_1_7") (pintype "passive"))
    )
    (net (code "3") (name "/BF_CLK18") (class "Default")
      (node (ref "U4") (pin "22") (pinfunction "SCK_22") (pintype "passive"))
      (node (ref "U9") (pin "4") (pinfunction "C_2_4") (pintype "passive"))
    )
    (net (code "4") (name "/BF_CLK19") (class "Default")
      (node (ref "U2") (pin "22") (pinfunction "SCK_22") (pintype "passive"))
      (node (ref "U9") (pin "1") (pinfunction "C_3_1") (pintype "passive"))
    )
    (net (code "5") (name "/BF_CLK20") (class "Default")
      (node (ref "U5") (pin "22") (pinfunction "SCK_22") (pintype "passive"))
      (node (ref "U9") (pin "38") (pinfunction "C_4_38") (pintype "passive"))
    )
    (net (code "6") (name "/BF_CLK21") (class "Default")
      (node (ref "U6") (pin "22") (pinfunction "SCK_22") (pintype "passive"))
      (node (ref "U9") (pin "35") (pinfunction "C_5_35") (pintype "passive"))
    )
    (net (code "7") (name "/BF_CLK22") (class "Default")
      (node (ref "U7") (pin "22") (pinfunction "SCK_22") (pintype "passive"))
      (node (ref "U9") (pin "32") (pinfunction "C_6_32") (pintype "passive"))
    )
    (net (code "8") (name "/BF_CLK23") (class "Default")
      (node (ref "U8") (pin "22") (pinfunction "SCK_22") (pintype "passive"))
      (node (ref "U9") (pin "29") (pinfunction "C_7_29") (pintype "passive"))
    )
    (net (code "9") (name "/BF_CLK24") (class "Default")
      (node (ref "U10") (pin "22") (pinfunction "SCK_22") (pintype "passive"))
      (node (ref "U9") (pin "26") (pinfunction "C_8_26") (pintype "passive"))
    )
    (net (code "10") (name "/BF_CLK25") (class "Default")
      (node (ref "U12") (pin "22") (pinfunction "SCK_22") (pintype "passive"))
      (node (ref "U9") (pin "23") (pinfunction "C_9_23") (pintype "passive"))
    )
    (net (code "11") (name "/BF_CLK26") (class "Default")
      (node (ref "U11") (pin "22") (pinfunction "SCK_22") (pintype "passive"))
      (node (ref "U9") (pin "20") (pinfunction "C_10_20") (pintype "passive"))
    )
    (net (code "12") (name "/BF_DAT16") (class "Default")
      (node (ref "R23") (pin "1") (pinfunction "1_1") (pintype "passive"))
      (node (ref "U1") (pin "23") (pinfunction "SDATA_23") (pintype "passive"))
      (node (ref "U9") (pin "9") (pinfunction "D_0_9") (pintype "passive"))
    )
    (net (code "13") (name "/BF_DAT17") (class "Default")
      (node (ref "U3") (pin "23") (pinfunction "SDATA_23") (pintype "passive"))
      (node (ref "U9") (pin "6") (pinfunction "D_1_6") (pintype "passive"))
    )
    (net (code "14") (name "/BF_DAT18") (class "Default")
      (node (ref "U4") (pin "23") (pinfunction "SDATA_23") (pintype "passive"))
      (node (ref "U9") (pin "3") (pinfunction "D_2_3") (pintype "passive"))
    )
    (net (code "15") (name "/BF_DAT19") (class "Default")
      (node (ref "U2") (pin "23") (pinfunction "SDATA_23") (pintype "passive"))
      (node (ref "U9") (pin "40") (pinfunction "D_3_40") (pintype "passive"))
    )
    (net (code "16") (name "/BF_DAT20") (class "Default")
      (node (ref "U5") (pin "23") (pinfunction "SDATA_23") (pintype "passive"))
      (node (ref "U9") (pin "37") (pinfunction "D_4_37") (pintype "passive"))
    )
    (net (code "17") (name "/BF_DAT21") (class "Default")
      (node (ref "U6") (pin "23") (pinfunction "SDATA_23") (pintype "passive"))
      (node (ref "U9") (pin "34") (pinfunction "D_5_34") (pintype "passive"))
    )
    (net (code "18") (name "/BF_DAT22") (class "Default")
      (node (ref "U7") (pin "23") (pinfunction "SDATA_23") (pintype "passive"))
      (node (ref "U9") (pin "31") (pinfunction "D_6_31") (pintype "passive"))
    )
    (net (code "19") (name "/BF_DAT23") (class "Default")
      (node (ref "U8") (pin "23") (pinfunction "SDATA_23") (pintype "passive"))
      (node (ref "U9") (pin "28") (pinfunction "D_7_28") (pintype "passive"))
    )
    (net (code "20") (name "/BF_DAT24") (class "Default")
      (node (ref "U10") (pin "23") (pinfunction "SDATA_23") (pintype "passive"))
      (node (ref "U9") (pin "25") (pinfunction "D_8_25") (pintype "passive"))
    )
    (net (code "21") (name "/BF_DAT25") (class "Default")
      (node (ref "U12") (pin "23") (pinfunction "SDATA_23") (pintype "passive"))
      (node (ref "U9") (pin "22") (pinfunction "D_9_22") (pintype "passive"))
    )
    (net (code "22") (name "/BF_DAT26") (class "Default")
      (node (ref "U11") (pin "23") (pinfunction "SDATA_23") (pintype "passive"))
      (node (ref "U9") (pin "19") (pinfunction "D_10_19") (pintype "passive"))
    )
    (net (code "23") (name "/GND_M3") (class "Default")
      (node (ref "C49") (pin "2") (pinfunction "2_2") (pintype "passive"))
      (node (ref "R24") (pin "1") (pinfunction "1_1") (pintype "passive"))
      (node (ref "R25") (pin "2") (pinfunction "2_2") (pintype "passive"))
      (node (ref "U9") (pin "41") (pinfunction "VSS_41") (pintype "passive"))
    )
    (net (code "24") (name "/PAR_3") (class "Default")
      (node (ref "U9") (pin "18") (pinfunction "PARITY_18") (pintype "passive"))
    )
    (net (code "25") (name "/PWR15") (class "Default")
      (node (ref "R25") (pin "1") (pinfunction "1_1") (pintype "passive"))
    )
    (net (code "26") (name "/PWR16") (class "Default")
      (node (ref "C1") (pin "2") (pinfunction "2_2") (pintype "passive"))
      (node (ref "C13") (pin "2") (pinfunction "2_2") (pintype "passive"))
      (node (ref "C14") (pin "2") (pinfunction "2_2") (pintype "passive"))
      (node (ref "C15") (pin "2") (pinfunction "2_2") (pintype "passive"))
      (node (ref "C2") (pin "2") (pinfunction "2_2") (pintype "passive"))
      (node (ref "C3") (pin "2") (pinfunction "2_2") (pintype "passive"))
      (node (ref "R24") (pin "2") (pinfunction "2_2") (pintype "passive"))
      (node (ref "U1") (pin "36") (pinfunction "EP_36") (pintype "passive"))
    )
    (net (code "27") (name "/PWR17") (class "Default")
      (node (ref "C1") (pin "1") (pinfunction "1_1") (pintype "passive"))
      (node (ref "C13") (pin "1") (pinfunction "1_1") (pintype "passive"))
      (node (ref "C14") (pin "1") (pinfunction "1_1") (pintype "passive"))
      (node (ref "C15") (pin "1") (pinfunction "1_1") (pintype "passive"))
      (node (ref "C16") (pin "2") (pinfunction "2_2") (pintype "passive"))
      (node (ref "C17") (pin "2") (pinfunction "2_2") (pintype "passive"))
      (node (ref "C18") (pin "2") (pinfunction "2_2") (pintype "passive"))
      (node (ref "C2") (pin "1") (pinfunction "1_1") (pintype "passive"))
      (node (ref "C3") (pin "1") (pinfunction "1_1") (pintype "passive"))
      (node (ref "C4") (pin "2") (pinfunction "2_2") (pintype "passive"))
      (node (ref "C5") (pin "2") (pinfunction "2_2") (pintype "passive"))
      (node (ref "C6") (pin "2") (pinfunction "2_2") (pintype "passive"))
      (node (ref "R23") (pin "2") (pinfunction "2_2") (pintype "passive"))
      (node (ref "U1") (pin "1") (pinfunction "VDD_1") (pintype "passive"))
      (node (ref "U1") (pin "10") (pinfunction "VDD_10") (pintype "passive"))
      (node (ref "U1") (pin "11") (pinfunction "VDD_11") (pintype "passive"))
      (node (ref "U1") (pin "12") (pinfunction "VDD_12") (pintype "passive"))
      (node (ref "U1") (pin "13") (pinfunction "VDD_13") (pintype "passive"))
      (node (ref "U1") (pin "14") (pinfunction "VDD_14") (pintype "passive"))
      (node (ref "U1") (pin "15") (pinfunction "VDD_15") (pintype "passive"))
      (node (ref "U1") (pin "16") (pinfunction "VDD_16") (pintype "passive"))
      (node (ref "U1") (pin "17") (pinfunction "VDD_17") (pintype "passive"))
      (node (ref "U1") (pin "18") (pinfunction "VDD_18") (pintype "passive"))
      (node (ref "U1") (pin "19") (pinfunction "VDD_19") (pintype "passive"))
      (node (ref "U1") (pin "2") (pinfunction "VDD_2") (pintype "passive"))
      (node (ref "U1") (pin "20") (pinfunction "VDD_20") (pintype "passive"))
      (node (ref "U1") (pin "21") (pinfunction "VDD_21") (pintype "passive"))
      (node (ref "U1") (pin "24") (pinfunction "VDD_24") (pintype "passive"))
      (node (ref "U1") (pin "25") (pinfunction "VDD_25") (pintype "passive"))
      (node (ref "U1") (pin "26") (pinfunction "VDD_26") (pintype "passive"))
      (node (ref "U1") (pin "27") (pinfunction "VDD_27") (pintype "passive"))
      (node (ref "U1") (pin "28") (pinfunction "VDD_28") (pintype "passive"))
      (node (ref "U1") (pin "29") (pinfunction "VDD_29") (pintype "passive"))
      (node (ref "U1") (pin "3") (pinfunction "VDD_3") (pintype "passive"))
      (node (ref "U1") (pin "30") (pinfunction "VDD_30") (pintype "passive"))
      (node (ref "U1") (pin "31") (pinfunction "VDD_31") (pintype "passive"))
      (node (ref "U1") (pin "32") (pinfunction "VDD_32") (pintype "passive"))
      (node (ref "U1") (pin "33") (pinfunction "VDD_33") (pintype "passive"))
      (node (ref "U1") (pin "34") (pinfunction "VDD_34") (pintype "passive"))
      (node (ref "U1") (pin "35") (pinfunction "VDD_35") (pintype "passive"))
      (node (ref "U1") (pin "4") (pinfunction "VDD_4") (pintype "passive"))
      (node (ref "U1") (pin "5") (pinfunction "VDD_5") (pintype "passive"))
      (node (ref "U1") (pin "6") (pinfunction "VDD_6") (pintype "passive"))
      (node (ref "U1") (pin "7") (pinfunction "VDD_7") (pintype "passive"))
      (node (ref "U1") (pin "8") (pinfunction "VDD_8") (pintype "passive"))
      (node (ref "U1") (pin "9") (pinfunction "VDD_9") (pintype "passive"))
      (node (ref "U3") (pin "36") (pinfunction "EP_36") (pintype "passive"))
      (node (ref "U9") (pin "8") (pinfunction "V_0_8") (pintype "passive"))
    )
    (net (code "28") (name "/PWR18") (class "Default")
      (node (ref "C16") (pin "1") (pinfunction "1_1") (pintype "passive"))
      (node (ref "C17") (pin "1") (pinfunction "1_1") (pintype "passive"))
      (node (ref "C18") (pin "1") (pinfunction "1_1") (pintype "passive"))
      (node (ref "C19") (pin "2") (pinfunction "2_2") (pintype "passive"))
      (node (ref "C20") (pin "2") (pinfunction "2_2") (pintype "passive"))
      (node (ref "C21") (pin "2") (pinfunction "2_2") (pintype "passive"))
      (node (ref "C4") (pin "1") (pinfunction "1_1") (pintype "passive"))
      (node (ref "C5") (pin "1") (pinfunction "1_1") (pintype "passive"))
      (node (ref "C6") (pin "1") (pinfunction "1_1") (pintype "passive"))
      (node (ref "C7") (pin "2") (pinfunction "2_2") (pintype "passive"))
      (node (ref "C8") (pin "2") (pinfunction "2_2") (pintype "passive"))
      (node (ref "C9") (pin "2") (pinfunction "2_2") (pintype "passive"))
      (node (ref "U3") (pin "1") (pinfunction "VDD_1") (pintype "passive"))
      (node (ref "U3") (pin "10") (pinfunction "VDD_10") (pintype "passive"))
      (node (ref "U3") (pin "11") (pinfunction "VDD_11") (pintype "passive"))
      (node (ref "U3") (pin "12") (pinfunction "VDD_12") (pintype "passive"))
      (node (ref "U3") (pin "13") (pinfunction "VDD_13") (pintype "passive"))
      (node (ref "U3") (pin "14") (pinfunction "VDD_14") (pintype "passive"))
      (node (ref "U3") (pin "15") (pinfunction "VDD_15") (pintype "passive"))
      (node (ref "U3") (pin "16") (pinfunction "VDD_16") (pintype "passive"))
      (node (ref "U3") (pin "17") (pinfunction "VDD_17") (pintype "passive"))
      (node (ref "U3") (pin "18") (pinfunction "VDD_18") (pintype "passive"))
      (node (ref "U3") (pin "19") (pinfunction "VDD_19") (pintype "passive"))
      (node (ref "U3") (pin "2") (pinfunction "VDD_2") (pintype "passive"))
      (node (ref "U3") (pin "20") (pinfunction "VDD_20") (pintype "passive"))
      (node (ref "U3") (pin "21") (pinfunction "VDD_21") (pintype "passive"))
      (node (ref "U3") (pin "24") (pinfunction "VDD_24") (pintype "passive"))
      (node (ref "U3") (pin "25") (pinfunction "VDD_25") (pintype "passive"))
      (node (ref "U3") (pin "26") (pinfunction "VDD_26") (pintype "passive"))
      (node (ref "U3") (pin "27") (pinfunction "VDD_27") (pintype "passive"))
      (node (ref "U3") (pin "28") (pinfunction "VDD_28") (pintype "passive"))
      (node (ref "U3") (pin "29") (pinfunction "VDD_29") (pintype "passive"))
      (node (ref "U3") (pin "3") (pinfunction "VDD_3") (pintype "passive"))
      (node (ref "U3") (pin "30") (pinfunction "VDD_30") (pintype "passive"))
      (node (ref "U3") (pin "31") (pinfunction "VDD_31") (pintype "passive"))
      (node (ref "U3") (pin "32") (pinfunction "VDD_32") (pintype "passive"))
      (node (ref "U3") (pin "33") (pinfunction "VDD_33") (pintype "passive"))
      (node (ref "U3") (pin "34") (pinfunction "VDD_34") (pintype "passive"))
      (node (ref "U3") (pin "35") (pinfunction "VDD_35") (pintype "passive"))
      (node (ref "U3") (pin "4") (pinfunction "VDD_4") (pintype "passive"))
      (node (ref "U3") (pin "5") (pinfunction "VDD_5") (pintype "passive"))
      (node (ref "U3") (pin "6") (pinfunction "VDD_6") (pintype "passive"))
      (node (ref "U3") (pin "7") (pinfunction "VDD_7") (pintype "passive"))
      (node (ref "U3") (pin "8") (pinfunction "VDD_8") (pintype "passive"))
      (node (ref "U3") (pin "9") (pinfunction "VDD_9") (pintype "passive"))
      (node (ref "U4") (pin "36") (pinfunction "EP_36") (pintype "passive"))
      (node (ref "U9") (pin "5") (pinfunction "V_1_5") (pintype "passive"))
    )
    (net (code "29") (name "/PWR19") (class "Default")
      (node (ref "C10") (pin "2") (pinfunction "2_2") (pintype "passive"))
      (node (ref "C11") (pin "2") (pinfunction "2_2") (pintype "passive"))
      (node (ref "C12") (pin "2") (pinfunction "2_2") (pintype "passive"))
      (node (ref "C19") (pin "1") (pinfunction "1_1") (pintype "passive"))
      (node (ref "C20") (pin "1") (pinfunction "1_1") (pintype "passive"))
      (node (ref "C21") (pin "1") (pinfunction "1_1") (pintype "passive"))
      (node (ref "C22") (pin "2") (pinfunction "2_2") (pintype "passive"))
      (node (ref "C23") (pin "2") (pinfunction "2_2") (pintype "passive"))
      (node (ref "C24") (pin "2") (pinfunction "2_2") (pintype "passive"))
      (node (ref "C7") (pin "1") (pinfunction "1_1") (pintype "passive"))
      (node (ref "C8") (pin "1") (pinfunction "1_1") (pintype "passive"))
      (node (ref "C9") (pin "1") (pinfunction "1_1") (pintype "passive"))
      (node (ref "U2") (pin "36") (pinfunction "EP_36") (pintype "passive"))
      (node (ref "U4") (pin "1") (pinfunction "VDD_1") (pintype "passive"))
      (node (ref "U4") (pin "10") (pinfunction "VDD_10") (pintype "passive"))
      (node (ref "U4") (pin "11") (pinfunction "VDD_11") (pintype "passive"))
      (node (ref "U4") (pin "12") (pinfunction "VDD_12") (pintype "passive"))
      (node (ref "U4") (pin "13") (pinfunction "VDD_13") (pintype "passive"))
      (node (ref "U4") (pin "14") (pinfunction "VDD_14") (pintype "passive"))
      (node (ref "U4") (pin "15") (pinfunction "VDD_15") (pintype "passive"))
      (node (ref "U4") (pin "16") (pinfunction "VDD_16") (pintype "passive"))
      (node (ref "U4") (pin "17") (pinfunction "VDD_17") (pintype "passive"))
      (node (ref "U4") (pin "18") (pinfunction "VDD_18") (pintype "passive"))
      (node (ref "U4") (pin "19") (pinfunction "VDD_19") (pintype "passive"))
      (node (ref "U4") (pin "2") (pinfunction "VDD_2") (pintype "passive"))
      (node (ref "U4") (pin "20") (pinfunction "VDD_20") (pintype "passive"))
      (node (ref "U4") (pin "21") (pinfunction "VDD_21") (pintype "passive"))
      (node (ref "U4") (pin "24") (pinfunction "VDD_24") (pintype "passive"))
      (node (ref "U4") (pin "25") (pinfunction "VDD_25") (pintype "passive"))
      (node (ref "U4") (pin "26") (pinfunction "VDD_26") (pintype "passive"))
      (node (ref "U4") (pin "27") (pinfunction "VDD_27") (pintype "passive"))
      (node (ref "U4") (pin "28") (pinfunction "VDD_28") (pintype "passive"))
      (node (ref "U4") (pin "29") (pinfunction "VDD_29") (pintype "passive"))
      (node (ref "U4") (pin "3") (pinfunction "VDD_3") (pintype "passive"))
      (node (ref "U4") (pin "30") (pinfunction "VDD_30") (pintype "passive"))
      (node (ref "U4") (pin "31") (pinfunction "VDD_31") (pintype "passive"))
      (node (ref "U4") (pin "32") (pinfunction "VDD_32") (pintype "passive"))
      (node (ref "U4") (pin "33") (pinfunction "VDD_33") (pintype "passive"))
      (node (ref "U4") (pin "34") (pinfunction "VDD_34") (pintype "passive"))
      (node (ref "U4") (pin "35") (pinfunction "VDD_35") (pintype "passive"))
      (node (ref "U4") (pin "4") (pinfunction "VDD_4") (pintype "passive"))
      (node (ref "U4") (pin "5") (pinfunction "VDD_5") (pintype "passive"))
      (node (ref "U4") (pin "6") (pinfunction "VDD_6") (pintype "passive"))
      (node (ref "U4") (pin "7") (pinfunction "VDD_7") (pintype "passive"))
      (node (ref "U4") (pin "8") (pinfunction "VDD_8") (pintype "passive"))
      (node (ref "U4") (pin "9") (pinfunction "VDD_9") (pintype "passive"))
      (node (ref "U9") (pin "2") (pinfunction "V_2_2") (pintype "passive"))
    )
    (net (code "30") (name "/PWR20") (class "Default")
      (node (ref "C10") (pin "1") (pinfunction "1_1") (pintype "passive"))
      (node (ref "C11") (pin "1") (pinfunction "1_1") (pintype "passive"))
      (node (ref "C12") (pin "1") (pinfunction "1_1") (pintype "passive"))
      (node (ref "C22") (pin "1") (pinfunction "1_1") (pintype "passive"))
      (node (ref "C23") (pin "1") (pinfunction "1_1") (pintype "passive"))
      (node (ref "C24") (pin "1") (pinfunction "1_1") (pintype "passive"))
      (node (ref "C25") (pin "2") (pinfunction "2_2") (pintype "passive"))
      (node (ref "C26") (pin "2") (pinfunction "2_2") (pintype "passive"))
      (node (ref "C27") (pin "2") (pinfunction "2_2") (pintype "passive"))
      (node (ref "C37") (pin "2") (pinfunction "2_2") (pintype "passive"))
      (node (ref "C38") (pin "2") (pinfunction "2_2") (pintype "passive"))
      (node (ref "C39") (pin "2") (pinfunction "2_2") (pintype "passive"))
      (node (ref "U2") (pin "1") (pinfunction "VDD_1") (pintype "passive"))
      (node (ref "U2") (pin "10") (pinfunction "VDD_10") (pintype "passive"))
      (node (ref "U2") (pin "11") (pinfunction "VDD_11") (pintype "passive"))
      (node (ref "U2") (pin "12") (pinfunction "VDD_12") (pintype "passive"))
      (node (ref "U2") (pin "13") (pinfunction "VDD_13") (pintype "passive"))
      (node (ref "U2") (pin "14") (pinfunction "VDD_14") (pintype "passive"))
      (node (ref "U2") (pin "15") (pinfunction "VDD_15") (pintype "passive"))
      (node (ref "U2") (pin "16") (pinfunction "VDD_16") (pintype "passive"))
      (node (ref "U2") (pin "17") (pinfunction "VDD_17") (pintype "passive"))
      (node (ref "U2") (pin "18") (pinfunction "VDD_18") (pintype "passive"))
      (node (ref "U2") (pin "19") (pinfunction "VDD_19") (pintype "passive"))
      (node (ref "U2") (pin "2") (pinfunction "VDD_2") (pintype "passive"))
      (node (ref "U2") (pin "20") (pinfunction "VDD_20") (pintype "passive"))
      (node (ref "U2") (pin "21") (pinfunction "VDD_21") (pintype "passive"))
      (node (ref "U2") (pin "24") (pinfunction "VDD_24") (pintype "passive"))
      (node (ref "U2") (pin "25") (pinfunction "VDD_25") (pintype "passive"))
      (node (ref "U2") (pin "26") (pinfunction "VDD_26") (pintype "passive"))
      (node (ref "U2") (pin "27") (pinfunction "VDD_27") (pintype "passive"))
      (node (ref "U2") (pin "28") (pinfunction "VDD_28") (pintype "passive"))
      (node (ref "U2") (pin "29") (pinfunction "VDD_29") (pintype "passive"))
      (node (ref "U2") (pin "3") (pinfunction "VDD_3") (pintype "passive"))
      (node (ref "U2") (pin "30") (pinfunction "VDD_30") (pintype "passive"))
      (node (ref "U2") (pin "31") (pinfunction "VDD_31") (pintype "passive"))
      (node (ref "U2") (pin "32") (pinfunction "VDD_32") (pintype "passive"))
      (node (ref "U2") (pin "33") (pinfunction "VDD_33") (pintype "passive"))
      (node (ref "U2") (pin "34") (pinfunction "VDD_34") (pintype "passive"))
      (node (ref "U2") (pin "35") (pinfunction "VDD_35") (pintype "passive"))
      (node (ref "U2") (pin "4") (pinfunction "VDD_4") (pintype "passive"))
      (node (ref "U2") (pin "5") (pinfunction "VDD_5") (pintype "passive"))
      (node (ref "U2") (pin "6") (pinfunction "VDD_6") (pintype "passive"))
      (node (ref "U2") (pin "7") (pinfunction "VDD_7") (pintype "passive"))
      (node (ref "U2") (pin "8") (pinfunction "VDD_8") (pintype "passive"))
      (node (ref "U2") (pin "9") (pinfunction "VDD_9") (pintype "passive"))
      (node (ref "U5") (pin "36") (pinfunction "EP_36") (pintype "passive"))
      (node (ref "U9") (pin "39") (pinfunction "V_3_39") (pintype "passive"))
    )
    (net (code "31") (name "/PWR21") (class "Default")
      (node (ref "C25") (pin "1") (pinfunction "1_1") (pintype "passive"))
      (node (ref "C26") (pin "1") (pinfunction "1_1") (pintype "passive"))
      (node (ref "C27") (pin "1") (pinfunction "1_1") (pintype "passive"))
      (node (ref "C28") (pin "2") (pinfunction "2_2") (pintype "passive"))
      (node (ref "C29") (pin "2") (pinfunction "2_2") (pintype "passive"))
      (node (ref "C30") (pin "2") (pinfunction "2_2") (pintype "passive"))
      (node (ref "C37") (pin "1") (pinfunction "1_1") (pintype "passive"))
      (node (ref "C38") (pin "1") (pinfunction "1_1") (pintype "passive"))
      (node (ref "C39") (pin "1") (pinfunction "1_1") (pintype "passive"))
      (node (ref "C40") (pin "2") (pinfunction "2_2") (pintype "passive"))
      (node (ref "C41") (pin "2") (pinfunction "2_2") (pintype "passive"))
      (node (ref "C42") (pin "2") (pinfunction "2_2") (pintype "passive"))
      (node (ref "U5") (pin "1") (pinfunction "VDD_1") (pintype "passive"))
      (node (ref "U5") (pin "10") (pinfunction "VDD_10") (pintype "passive"))
      (node (ref "U5") (pin "11") (pinfunction "VDD_11") (pintype "passive"))
      (node (ref "U5") (pin "12") (pinfunction "VDD_12") (pintype "passive"))
      (node (ref "U5") (pin "13") (pinfunction "VDD_13") (pintype "passive"))
      (node (ref "U5") (pin "14") (pinfunction "VDD_14") (pintype "passive"))
      (node (ref "U5") (pin "15") (pinfunction "VDD_15") (pintype "passive"))
      (node (ref "U5") (pin "16") (pinfunction "VDD_16") (pintype "passive"))
      (node (ref "U5") (pin "17") (pinfunction "VDD_17") (pintype "passive"))
      (node (ref "U5") (pin "18") (pinfunction "VDD_18") (pintype "passive"))
      (node (ref "U5") (pin "19") (pinfunction "VDD_19") (pintype "passive"))
      (node (ref "U5") (pin "2") (pinfunction "VDD_2") (pintype "passive"))
      (node (ref "U5") (pin "20") (pinfunction "VDD_20") (pintype "passive"))
      (node (ref "U5") (pin "21") (pinfunction "VDD_21") (pintype "passive"))
      (node (ref "U5") (pin "24") (pinfunction "VDD_24") (pintype "passive"))
      (node (ref "U5") (pin "25") (pinfunction "VDD_25") (pintype "passive"))
      (node (ref "U5") (pin "26") (pinfunction "VDD_26") (pintype "passive"))
      (node (ref "U5") (pin "27") (pinfunction "VDD_27") (pintype "passive"))
      (node (ref "U5") (pin "28") (pinfunction "VDD_28") (pintype "passive"))
      (node (ref "U5") (pin "29") (pinfunction "VDD_29") (pintype "passive"))
      (node (ref "U5") (pin "3") (pinfunction "VDD_3") (pintype "passive"))
      (node (ref "U5") (pin "30") (pinfunction "VDD_30") (pintype "passive"))
      (node (ref "U5") (pin "31") (pinfunction "VDD_31") (pintype "passive"))
      (node (ref "U5") (pin "32") (pinfunction "VDD_32") (pintype "passive"))
      (node (ref "U5") (pin "33") (pinfunction "VDD_33") (pintype "passive"))
      (node (ref "U5") (pin "34") (pinfunction "VDD_34") (pintype "passive"))
      (node (ref "U5") (pin "35") (pinfunction "VDD_35") (pintype "passive"))
      (node (ref "U5") (pin "4") (pinfunction "VDD_4") (pintype "passive"))
      (node (ref "U5") (pin "5") (pinfunction "VDD_5") (pintype "passive"))
      (node (ref "U5") (pin "6") (pinfunction "VDD_6") (pintype "passive"))
      (node (ref "U5") (pin "7") (pinfunction "VDD_7") (pintype "passive"))
      (node (ref "U5") (pin "8") (pinfunction "VDD_8") (pintype "passive"))
      (node (ref "U5") (pin "9") (pinfunction "VDD_9") (pintype "passive"))
      (node (ref "U6") (pin "36") (pinfunction "EP_36") (pintype "passive"))
      (node (ref "U9") (pin "36") (pinfunction "V_4_36") (pintype "passive"))
    )
    (net (code "32") (name "/PWR22") (class "Default")
      (node (ref "C28") (pin "1") (pinfunction "1_1") (pintype "passive"))
      (node (ref "C29") (pin "1") (pinfunction "1_1") (pintype "passive"))
      (node (ref "C30") (pin "1") (pinfunction "1_1") (pintype "passive"))
      (node (ref "C31") (pin "2") (pinfunction "2_2") (pintype "passive"))
      (node (ref "C32") (pin "2") (pinfunction "2_2") (pintype "passive"))
      (node (ref "C33") (pin "2") (pinfunction "2_2") (pintype "passive"))
      (node (ref "C40") (pin "1") (pinfunction "1_1") (pintype "passive"))
      (node (ref "C41") (pin "1") (pinfunction "1_1") (pintype "passive"))
      (node (ref "C42") (pin "1") (pinfunction "1_1") (pintype "passive"))
      (node (ref "C43") (pin "2") (pinfunction "2_2") (pintype "passive"))
      (node (ref "C44") (pin "2") (pinfunction "2_2") (pintype "passive"))
      (node (ref "C45") (pin "2") (pinfunction "2_2") (pintype "passive"))
      (node (ref "U6") (pin "1") (pinfunction "VDD_1") (pintype "passive"))
      (node (ref "U6") (pin "10") (pinfunction "VDD_10") (pintype "passive"))
      (node (ref "U6") (pin "11") (pinfunction "VDD_11") (pintype "passive"))
      (node (ref "U6") (pin "12") (pinfunction "VDD_12") (pintype "passive"))
      (node (ref "U6") (pin "13") (pinfunction "VDD_13") (pintype "passive"))
      (node (ref "U6") (pin "14") (pinfunction "VDD_14") (pintype "passive"))
      (node (ref "U6") (pin "15") (pinfunction "VDD_15") (pintype "passive"))
      (node (ref "U6") (pin "16") (pinfunction "VDD_16") (pintype "passive"))
      (node (ref "U6") (pin "17") (pinfunction "VDD_17") (pintype "passive"))
      (node (ref "U6") (pin "18") (pinfunction "VDD_18") (pintype "passive"))
      (node (ref "U6") (pin "19") (pinfunction "VDD_19") (pintype "passive"))
      (node (ref "U6") (pin "2") (pinfunction "VDD_2") (pintype "passive"))
      (node (ref "U6") (pin "20") (pinfunction "VDD_20") (pintype "passive"))
      (node (ref "U6") (pin "21") (pinfunction "VDD_21") (pintype "passive"))
      (node (ref "U6") (pin "24") (pinfunction "VDD_24") (pintype "passive"))
      (node (ref "U6") (pin "25") (pinfunction "VDD_25") (pintype "passive"))
      (node (ref "U6") (pin "26") (pinfunction "VDD_26") (pintype "passive"))
      (node (ref "U6") (pin "27") (pinfunction "VDD_27") (pintype "passive"))
      (node (ref "U6") (pin "28") (pinfunction "VDD_28") (pintype "passive"))
      (node (ref "U6") (pin "29") (pinfunction "VDD_29") (pintype "passive"))
      (node (ref "U6") (pin "3") (pinfunction "VDD_3") (pintype "passive"))
      (node (ref "U6") (pin "30") (pinfunction "VDD_30") (pintype "passive"))
      (node (ref "U6") (pin "31") (pinfunction "VDD_31") (pintype "passive"))
      (node (ref "U6") (pin "32") (pinfunction "VDD_32") (pintype "passive"))
      (node (ref "U6") (pin "33") (pinfunction "VDD_33") (pintype "passive"))
      (node (ref "U6") (pin "34") (pinfunction "VDD_34") (pintype "passive"))
      (node (ref "U6") (pin "35") (pinfunction "VDD_35") (pintype "passive"))
      (node (ref "U6") (pin "4") (pinfunction "VDD_4") (pintype "passive"))
      (node (ref "U6") (pin "5") (pinfunction "VDD_5") (pintype "passive"))
      (node (ref "U6") (pin "6") (pinfunction "VDD_6") (pintype "passive"))
      (node (ref "U6") (pin "7") (pinfunction "VDD_7") (pintype "passive"))
      (node (ref "U6") (pin "8") (pinfunction "VDD_8") (pintype "passive"))
      (node (ref "U6") (pin "9") (pinfunction "VDD_9") (pintype "passive"))
      (node (ref "U7") (pin "36") (pinfunction "EP_36") (pintype "passive"))
      (node (ref "U9") (pin "33") (pinfunction "V_5_33") (pintype "passive"))
    )
    (net (code "33") (name "/PWR23") (class "Default")
      (node (ref "C31") (pin "1") (pinfunction "1_1") (pintype "passive"))
      (node (ref "C32") (pin "1") (pinfunction "1_1") (pintype "passive"))
      (node (ref "C33") (pin "1") (pinfunction "1_1") (pintype "passive"))
      (node (ref "C34") (pin "2") (pinfunction "2_2") (pintype "passive"))
      (node (ref "C35") (pin "2") (pinfunction "2_2") (pintype "passive"))
      (node (ref "C36") (pin "2") (pinfunction "2_2") (pintype "passive"))
      (node (ref "C43") (pin "1") (pinfunction "1_1") (pintype "passive"))
      (node (ref "C44") (pin "1") (pinfunction "1_1") (pintype "passive"))
      (node (ref "C45") (pin "1") (pinfunction "1_1") (pintype "passive"))
      (node (ref "C46") (pin "2") (pinfunction "2_2") (pintype "passive"))
      (node (ref "C47") (pin "2") (pinfunction "2_2") (pintype "passive"))
      (node (ref "C48") (pin "2") (pinfunction "2_2") (pintype "passive"))
      (node (ref "U7") (pin "1") (pinfunction "VDD_1") (pintype "passive"))
      (node (ref "U7") (pin "10") (pinfunction "VDD_10") (pintype "passive"))
      (node (ref "U7") (pin "11") (pinfunction "VDD_11") (pintype "passive"))
      (node (ref "U7") (pin "12") (pinfunction "VDD_12") (pintype "passive"))
      (node (ref "U7") (pin "13") (pinfunction "VDD_13") (pintype "passive"))
      (node (ref "U7") (pin "14") (pinfunction "VDD_14") (pintype "passive"))
      (node (ref "U7") (pin "15") (pinfunction "VDD_15") (pintype "passive"))
      (node (ref "U7") (pin "16") (pinfunction "VDD_16") (pintype "passive"))
      (node (ref "U7") (pin "17") (pinfunction "VDD_17") (pintype "passive"))
      (node (ref "U7") (pin "18") (pinfunction "VDD_18") (pintype "passive"))
      (node (ref "U7") (pin "19") (pinfunction "VDD_19") (pintype "passive"))
      (node (ref "U7") (pin "2") (pinfunction "VDD_2") (pintype "passive"))
      (node (ref "U7") (pin "20") (pinfunction "VDD_20") (pintype "passive"))
      (node (ref "U7") (pin "21") (pinfunction "VDD_21") (pintype "passive"))
      (node (ref "U7") (pin "24") (pinfunction "VDD_24") (pintype "passive"))
      (node (ref "U7") (pin "25") (pinfunction "VDD_25") (pintype "passive"))
      (node (ref "U7") (pin "26") (pinfunction "VDD_26") (pintype "passive"))
      (node (ref "U7") (pin "27") (pinfunction "VDD_27") (pintype "passive"))
      (node (ref "U7") (pin "28") (pinfunction "VDD_28") (pintype "passive"))
      (node (ref "U7") (pin "29") (pinfunction "VDD_29") (pintype "passive"))
      (node (ref "U7") (pin "3") (pinfunction "VDD_3") (pintype "passive"))
      (node (ref "U7") (pin "30") (pinfunction "VDD_30") (pintype "passive"))
      (node (ref "U7") (pin "31") (pinfunction "VDD_31") (pintype "passive"))
      (node (ref "U7") (pin "32") (pinfunction "VDD_32") (pintype "passive"))
      (node (ref "U7") (pin "33") (pinfunction "VDD_33") (pintype "passive"))
      (node (ref "U7") (pin "34") (pinfunction "VDD_34") (pintype "passive"))
      (node (ref "U7") (pin "35") (pinfunction "VDD_35") (pintype "passive"))
      (node (ref "U7") (pin "4") (pinfunction "VDD_4") (pintype "passive"))
      (node (ref "U7") (pin "5") (pinfunction "VDD_5") (pintype "passive"))
      (node (ref "U7") (pin "6") (pinfunction "VDD_6") (pintype "passive"))
      (node (ref "U7") (pin "7") (pinfunction "VDD_7") (pintype "passive"))
      (node (ref "U7") (pin "8") (pinfunction "VDD_8") (pintype "passive"))
      (node (ref "U7") (pin "9") (pinfunction "VDD_9") (pintype "passive"))
      (node (ref "U8") (pin "36") (pinfunction "EP_36") (pintype "passive"))
      (node (ref "U9") (pin "30") (pinfunction "V_6_30") (pintype "passive"))
    )
    (net (code "34") (name "/PWR24") (class "Default")
      (node (ref "C34") (pin "1") (pinfunction "1_1") (pintype "passive"))
      (node (ref "C35") (pin "1") (pinfunction "1_1") (pintype "passive"))
      (node (ref "C36") (pin "1") (pinfunction "1_1") (pintype "passive"))
      (node (ref "C46") (pin "1") (pinfunction "1_1") (pintype "passive"))
      (node (ref "C47") (pin "1") (pinfunction "1_1") (pintype "passive"))
      (node (ref "C48") (pin "1") (pinfunction "1_1") (pintype "passive"))
      (node (ref "C50") (pin "2") (pinfunction "2_2") (pintype "passive"))
      (node (ref "C51") (pin "2") (pinfunction "2_2") (pintype "passive"))
      (node (ref "C52") (pin "2") (pinfunction "2_2") (pintype "passive"))
      (node (ref "C59") (pin "2") (pinfunction "2_2") (pintype "passive"))
      (node (ref "C60") (pin "2") (pinfunction "2_2") (pintype "passive"))
      (node (ref "C61") (pin "2") (pinfunction "2_2") (pintype "passive"))
      (node (ref "U10") (pin "36") (pinfunction "EP_36") (pintype "passive"))
      (node (ref "U8") (pin "1") (pinfunction "VDD_1") (pintype "passive"))
      (node (ref "U8") (pin "10") (pinfunction "VDD_10") (pintype "passive"))
      (node (ref "U8") (pin "11") (pinfunction "VDD_11") (pintype "passive"))
      (node (ref "U8") (pin "12") (pinfunction "VDD_12") (pintype "passive"))
      (node (ref "U8") (pin "13") (pinfunction "VDD_13") (pintype "passive"))
      (node (ref "U8") (pin "14") (pinfunction "VDD_14") (pintype "passive"))
      (node (ref "U8") (pin "15") (pinfunction "VDD_15") (pintype "passive"))
      (node (ref "U8") (pin "16") (pinfunction "VDD_16") (pintype "passive"))
      (node (ref "U8") (pin "17") (pinfunction "VDD_17") (pintype "passive"))
      (node (ref "U8") (pin "18") (pinfunction "VDD_18") (pintype "passive"))
      (node (ref "U8") (pin "19") (pinfunction "VDD_19") (pintype "passive"))
      (node (ref "U8") (pin "2") (pinfunction "VDD_2") (pintype "passive"))
      (node (ref "U8") (pin "20") (pinfunction "VDD_20") (pintype "passive"))
      (node (ref "U8") (pin "21") (pinfunction "VDD_21") (pintype "passive"))
      (node (ref "U8") (pin "24") (pinfunction "VDD_24") (pintype "passive"))
      (node (ref "U8") (pin "25") (pinfunction "VDD_25") (pintype "passive"))
      (node (ref "U8") (pin "26") (pinfunction "VDD_26") (pintype "passive"))
      (node (ref "U8") (pin "27") (pinfunction "VDD_27") (pintype "passive"))
      (node (ref "U8") (pin "28") (pinfunction "VDD_28") (pintype "passive"))
      (node (ref "U8") (pin "29") (pinfunction "VDD_29") (pintype "passive"))
      (node (ref "U8") (pin "3") (pinfunction "VDD_3") (pintype "passive"))
      (node (ref "U8") (pin "30") (pinfunction "VDD_30") (pintype "passive"))
      (node (ref "U8") (pin "31") (pinfunction "VDD_31") (pintype "passive"))
      (node (ref "U8") (pin "32") (pinfunction "VDD_32") (pintype "passive"))
      (node (ref "U8") (pin "33") (pinfunction "VDD_33") (pintype "passive"))
      (node (ref "U8") (pin "34") (pinfunction "VDD_34") (pintype "passive"))
      (node (ref "U8") (pin "35") (pinfunction "VDD_35") (pintype "passive"))
      (node (ref "U8") (pin "4") (pinfunction "VDD_4") (pintype "passive"))
      (node (ref "U8") (pin "5") (pinfunction "VDD_5") (pintype "passive"))
      (node (ref "U8") (pin "6") (pinfunction "VDD_6") (pintype "passive"))
      (node (ref "U8") (pin "7") (pinfunction "VDD_7") (pintype "passive"))
      (node (ref "U8") (pin "8") (pinfunction "VDD_8") (pintype "passive"))
      (node (ref "U8") (pin "9") (pinfunction "VDD_9") (pintype "passive"))
      (node (ref "U9") (pin "27") (pinfunction "V_7_27") (pintype "passive"))
    )
    (net (code "35") (name "/PWR25") (class "Default")
      (node (ref "C50") (pin "1") (pinfunction "1_1") (pintype "passive"))
      (node (ref "C51") (pin "1") (pinfunction "1_1") (pintype "passive"))
      (node (ref "C52") (pin "1") (pinfunction "1_1") (pintype "passive"))
      (node (ref "C53") (pin "2") (pinfunction "2_2") (pintype "passive"))
      (node (ref "C54") (pin "2") (pinfunction "2_2") (pintype "passive"))
      (node (ref "C55") (pin "2") (pinfunction "2_2") (pintype "passive"))
      (node (ref "C59") (pin "1") (pinfunction "1_1") (pintype "passive"))
      (node (ref "C60") (pin "1") (pinfunction "1_1") (pintype "passive"))
      (node (ref "C61") (pin "1") (pinfunction "1_1") (pintype "passive"))
      (node (ref "C62") (pin "2") (pinfunction "2_2") (pintype "passive"))
      (node (ref "C63") (pin "2") (pinfunction "2_2") (pintype "passive"))
      (node (ref "C64") (pin "2") (pinfunction "2_2") (pintype "passive"))
      (node (ref "U10") (pin "1") (pinfunction "VDD_1") (pintype "passive"))
      (node (ref "U10") (pin "10") (pinfunction "VDD_10") (pintype "passive"))
      (node (ref "U10") (pin "11") (pinfunction "VDD_11") (pintype "passive"))
      (node (ref "U10") (pin "12") (pinfunction "VDD_12") (pintype "passive"))
      (node (ref "U10") (pin "13") (pinfunction "VDD_13") (pintype "passive"))
      (node (ref "U10") (pin "14") (pinfunction "VDD_14") (pintype "passive"))
      (node (ref "U10") (pin "15") (pinfunction "VDD_15") (pintype "passive"))
      (node (ref "U10") (pin "16") (pinfunction "VDD_16") (pintype "passive"))
      (node (ref "U10") (pin "17") (pinfunction "VDD_17") (pintype "passive"))
      (node (ref "U10") (pin "18") (pinfunction "VDD_18") (pintype "passive"))
      (node (ref "U10") (pin "19") (pinfunction "VDD_19") (pintype "passive"))
      (node (ref "U10") (pin "2") (pinfunction "VDD_2") (pintype "passive"))
      (node (ref "U10") (pin "20") (pinfunction "VDD_20") (pintype "passive"))
      (node (ref "U10") (pin "21") (pinfunction "VDD_21") (pintype "passive"))
      (node (ref "U10") (pin "24") (pinfunction "VDD_24") (pintype "passive"))
      (node (ref "U10") (pin "25") (pinfunction "VDD_25") (pintype "passive"))
      (node (ref "U10") (pin "26") (pinfunction "VDD_26") (pintype "passive"))
      (node (ref "U10") (pin "27") (pinfunction "VDD_27") (pintype "passive"))
      (node (ref "U10") (pin "28") (pinfunction "VDD_28") (pintype "passive"))
      (node (ref "U10") (pin "29") (pinfunction "VDD_29") (pintype "passive"))
      (node (ref "U10") (pin "3") (pinfunction "VDD_3") (pintype "passive"))
      (node (ref "U10") (pin "30") (pinfunction "VDD_30") (pintype "passive"))
      (node (ref "U10") (pin "31") (pinfunction "VDD_31") (pintype "passive"))
      (node (ref "U10") (pin "32") (pinfunction "VDD_32") (pintype "passive"))
      (node (ref "U10") (pin "33") (pinfunction "VDD_33") (pintype "passive"))
      (node (ref "U10") (pin "34") (pinfunction "VDD_34") (pintype "passive"))
      (node (ref "U10") (pin "35") (pinfunction "VDD_35") (pintype "passive"))
      (node (ref "U10") (pin "4") (pinfunction "VDD_4") (pintype "passive"))
      (node (ref "U10") (pin "5") (pinfunction "VDD_5") (pintype "passive"))
      (node (ref "U10") (pin "6") (pinfunction "VDD_6") (pintype "passive"))
      (node (ref "U10") (pin "7") (pinfunction "VDD_7") (pintype "passive"))
      (node (ref "U10") (pin "8") (pinfunction "VDD_8") (pintype "passive"))
      (node (ref "U10") (pin "9") (pinfunction "VDD_9") (pintype "passive"))
      (node (ref "U12") (pin "36") (pinfunction "EP_36") (pintype "passive"))
      (node (ref "U9") (pin "24") (pinfunction "V_8_24") (pintype "passive"))
    )
    (net (code "36") (name "/PWR26") (class "Default")
      (node (ref "C53") (pin "1") (pinfunction "1_1") (pintype "passive"))
      (node (ref "C54") (pin "1") (pinfunction "1_1") (pintype "passive"))
      (node (ref "C55") (pin "1") (pinfunction "1_1") (pintype "passive"))
      (node (ref "C56") (pin "2") (pinfunction "2_2") (pintype "passive"))
      (node (ref "C57") (pin "2") (pinfunction "2_2") (pintype "passive"))
      (node (ref "C58") (pin "2") (pinfunction "2_2") (pintype "passive"))
      (node (ref "C62") (pin "1") (pinfunction "1_1") (pintype "passive"))
      (node (ref "C63") (pin "1") (pinfunction "1_1") (pintype "passive"))
      (node (ref "C64") (pin "1") (pinfunction "1_1") (pintype "passive"))
      (node (ref "C65") (pin "2") (pinfunction "2_2") (pintype "passive"))
      (node (ref "C66") (pin "2") (pinfunction "2_2") (pintype "passive"))
      (node (ref "C67") (pin "2") (pinfunction "2_2") (pintype "passive"))
      (node (ref "U11") (pin "36") (pinfunction "EP_36") (pintype "passive"))
      (node (ref "U12") (pin "1") (pinfunction "VDD_1") (pintype "passive"))
      (node (ref "U12") (pin "10") (pinfunction "VDD_10") (pintype "passive"))
      (node (ref "U12") (pin "11") (pinfunction "VDD_11") (pintype "passive"))
      (node (ref "U12") (pin "12") (pinfunction "VDD_12") (pintype "passive"))
      (node (ref "U12") (pin "13") (pinfunction "VDD_13") (pintype "passive"))
      (node (ref "U12") (pin "14") (pinfunction "VDD_14") (pintype "passive"))
      (node (ref "U12") (pin "15") (pinfunction "VDD_15") (pintype "passive"))
      (node (ref "U12") (pin "16") (pinfunction "VDD_16") (pintype "passive"))
      (node (ref "U12") (pin "17") (pinfunction "VDD_17") (pintype "passive"))
      (node (ref "U12") (pin "18") (pinfunction "VDD_18") (pintype "passive"))
      (node (ref "U12") (pin "19") (pinfunction "VDD_19") (pintype "passive"))
      (node (ref "U12") (pin "2") (pinfunction "VDD_2") (pintype "passive"))
      (node (ref "U12") (pin "20") (pinfunction "VDD_20") (pintype "passive"))
      (node (ref "U12") (pin "21") (pinfunction "VDD_21") (pintype "passive"))
      (node (ref "U12") (pin "24") (pinfunction "VDD_24") (pintype "passive"))
      (node (ref "U12") (pin "25") (pinfunction "VDD_25") (pintype "passive"))
      (node (ref "U12") (pin "26") (pinfunction "VDD_26") (pintype "passive"))
      (node (ref "U12") (pin "27") (pinfunction "VDD_27") (pintype "passive"))
      (node (ref "U12") (pin "28") (pinfunction "VDD_28") (pintype "passive"))
      (node (ref "U12") (pin "29") (pinfunction "VDD_29") (pintype "passive"))
      (node (ref "U12") (pin "3") (pinfunction "VDD_3") (pintype "passive"))
      (node (ref "U12") (pin "30") (pinfunction "VDD_30") (pintype "passive"))
      (node (ref "U12") (pin "31") (pinfunction "VDD_31") (pintype "passive"))
      (node (ref "U12") (pin "32") (pinfunction "VDD_32") (pintype "passive"))
      (node (ref "U12") (pin "33") (pinfunction "VDD_33") (pintype "passive"))
      (node (ref "U12") (pin "34") (pinfunction "VDD_34") (pintype "passive"))
      (node (ref "U12") (pin "35") (pinfunction "VDD_35") (pintype "passive"))
      (node (ref "U12") (pin "4") (pinfunction "VDD_4") (pintype "passive"))
      (node (ref "U12") (pin "5") (pinfunction "VDD_5") (pintype "passive"))
      (node (ref "U12") (pin "6") (pinfunction "VDD_6") (pintype "passive"))
      (node (ref "U12") (pin "7") (pinfunction "VDD_7") (pintype "passive"))
      (node (ref "U12") (pin "8") (pinfunction "VDD_8") (pintype "passive"))
      (node (ref "U12") (pin "9") (pinfunction "VDD_9") (pintype "passive"))
      (node (ref "U9") (pin "21") (pinfunction "V_9_21") (pintype "passive"))
    )
    (net (code "37") (name "/RX0_3") (class "Default")
      (node (ref "U9") (pin "12") (pinfunction "RX_0_12") (pintype "passive"))
    )
    (net (code "38") (name "/RX1_3") (class "Default")
      (node (ref "U9") (pin "14") (pinfunction "RX_1_14") (pintype "passive"))
    )
    (net (code "39") (name "/RX2_3") (class "Default")
      (node (ref "U9") (pin "16") (pinfunction "RX_2_16") (pintype "passive"))
    )
    (net (code "40") (name "/TX0_3") (class "Default")
      (node (ref "U9") (pin "11") (pinfunction "TX_0_11") (pintype "passive"))
    )
    (net (code "41") (name "/TX1_3") (class "Default")
      (node (ref "U9") (pin "13") (pinfunction "TX_1_13") (pintype "passive"))
    )
    (net (code "42") (name "/TX2_3") (class "Default")
      (node (ref "U9") (pin "15") (pinfunction "TX_2_15") (pintype "passive"))
    )
    (net (code "43") (name "/VCC") (class "Default")
      (node (ref "C49") (pin "1") (pinfunction "1_1") (pintype "passive"))
      (node (ref "C56") (pin "1") (pinfunction "1_1") (pintype "passive"))
      (node (ref "C57") (pin "1") (pinfunction "1_1") (pintype "passive"))
      (node (ref "C58") (pin "1") (pinfunction "1_1") (pintype "passive"))
      (node (ref "C65") (pin "1") (pinfunction "1_1") (pintype "passive"))
      (node (ref "C66") (pin "1") (pinfunction "1_1") (pintype "passive"))
      (node (ref "C67") (pin "1") (pinfunction "1_1") (pintype "passive"))
      (node (ref "U11") (pin "1") (pinfunction "VDD_1") (pintype "passive"))
      (node (ref "U11") (pin "10") (pinfunction "VDD_10") (pintype "passive"))
      (node (ref "U11") (pin "11") (pinfunction "VDD_11") (pintype "passive"))
      (node (ref "U11") (pin "12") (pinfunction "VDD_12") (pintype "passive"))
      (node (ref "U11") (pin "13") (pinfunction "VDD_13") (pintype "passive"))
      (node (ref "U11") (pin "14") (pinfunction "VDD_14") (pintype "passive"))
      (node (ref "U11") (pin "15") (pinfunction "VDD_15") (pintype "passive"))
      (node (ref "U11") (pin "16") (pinfunction "VDD_16") (pintype "passive"))
      (node (ref "U11") (pin "17") (pinfunction "VDD_17") (pintype "passive"))
      (node (ref "U11") (pin "18") (pinfunction "VDD_18") (pintype "passive"))
      (node (ref "U11") (pin "19") (pinfunction "VDD_19") (pintype "passive"))
      (node (ref "U11") (pin "2") (pinfunction "VDD_2") (pintype "passive"))
      (node (ref "U11") (pin "20") (pinfunction "VDD_20") (pintype "passive"))
      (node (ref "U11") (pin "21") (pinfunction "VDD_21") (pintype "passive"))
      (node (ref "U11") (pin "24") (pinfunction "VDD_24") (pintype "passive"))
      (node (ref "U11") (pin "25") (pinfunction "VDD_25") (pintype "passive"))
      (node (ref "U11") (pin "26") (pinfunction "VDD_26") (pintype "passive"))
      (node (ref "U11") (pin "27") (pinfunction "VDD_27") (pintype "passive"))
      (node (ref "U11") (pin "28") (pinfunction "VDD_28") (pintype "passive"))
      (node (ref "U11") (pin "29") (pinfunction "VDD_29") (pintype "passive"))
      (node (ref "U11") (pin "3") (pinfunction "VDD_3") (pintype "passive"))
      (node (ref "U11") (pin "30") (pinfunction "VDD_30") (pintype "passive"))
      (node (ref "U11") (pin "31") (pinfunction "VDD_31") (pintype "passive"))
      (node (ref "U11") (pin "32") (pinfunction "VDD_32") (pintype "passive"))
      (node (ref "U11") (pin "33") (pinfunction "VDD_33") (pintype "passive"))
      (node (ref "U11") (pin "34") (pinfunction "VDD_34") (pintype "passive"))
      (node (ref "U11") (pin "35") (pinfunction "VDD_35") (pintype "passive"))
      (node (ref "U11") (pin "4") (pinfunction "VDD_4") (pintype "passive"))
      (node (ref "U11") (pin "5") (pinfunction "VDD_5") (pintype "passive"))
      (node (ref "U11") (pin "6") (pinfunction "VDD_6") (pintype "passive"))
      (node (ref "U11") (pin "7") (pinfunction "VDD_7") (pintype "passive"))
      (node (ref "U11") (pin "8") (pinfunction "VDD_8") (pintype "passive"))
      (node (ref "U11") (pin "9") (pinfunction "VDD_9") (pintype "passive"))
      (node (ref "U9") (pin "17") (pinfunction "VDD_17") (pintype "passive"))
    )
  )
)
